# dmfboard.net
KiCad netlist of a schematic drawn in EAGLE
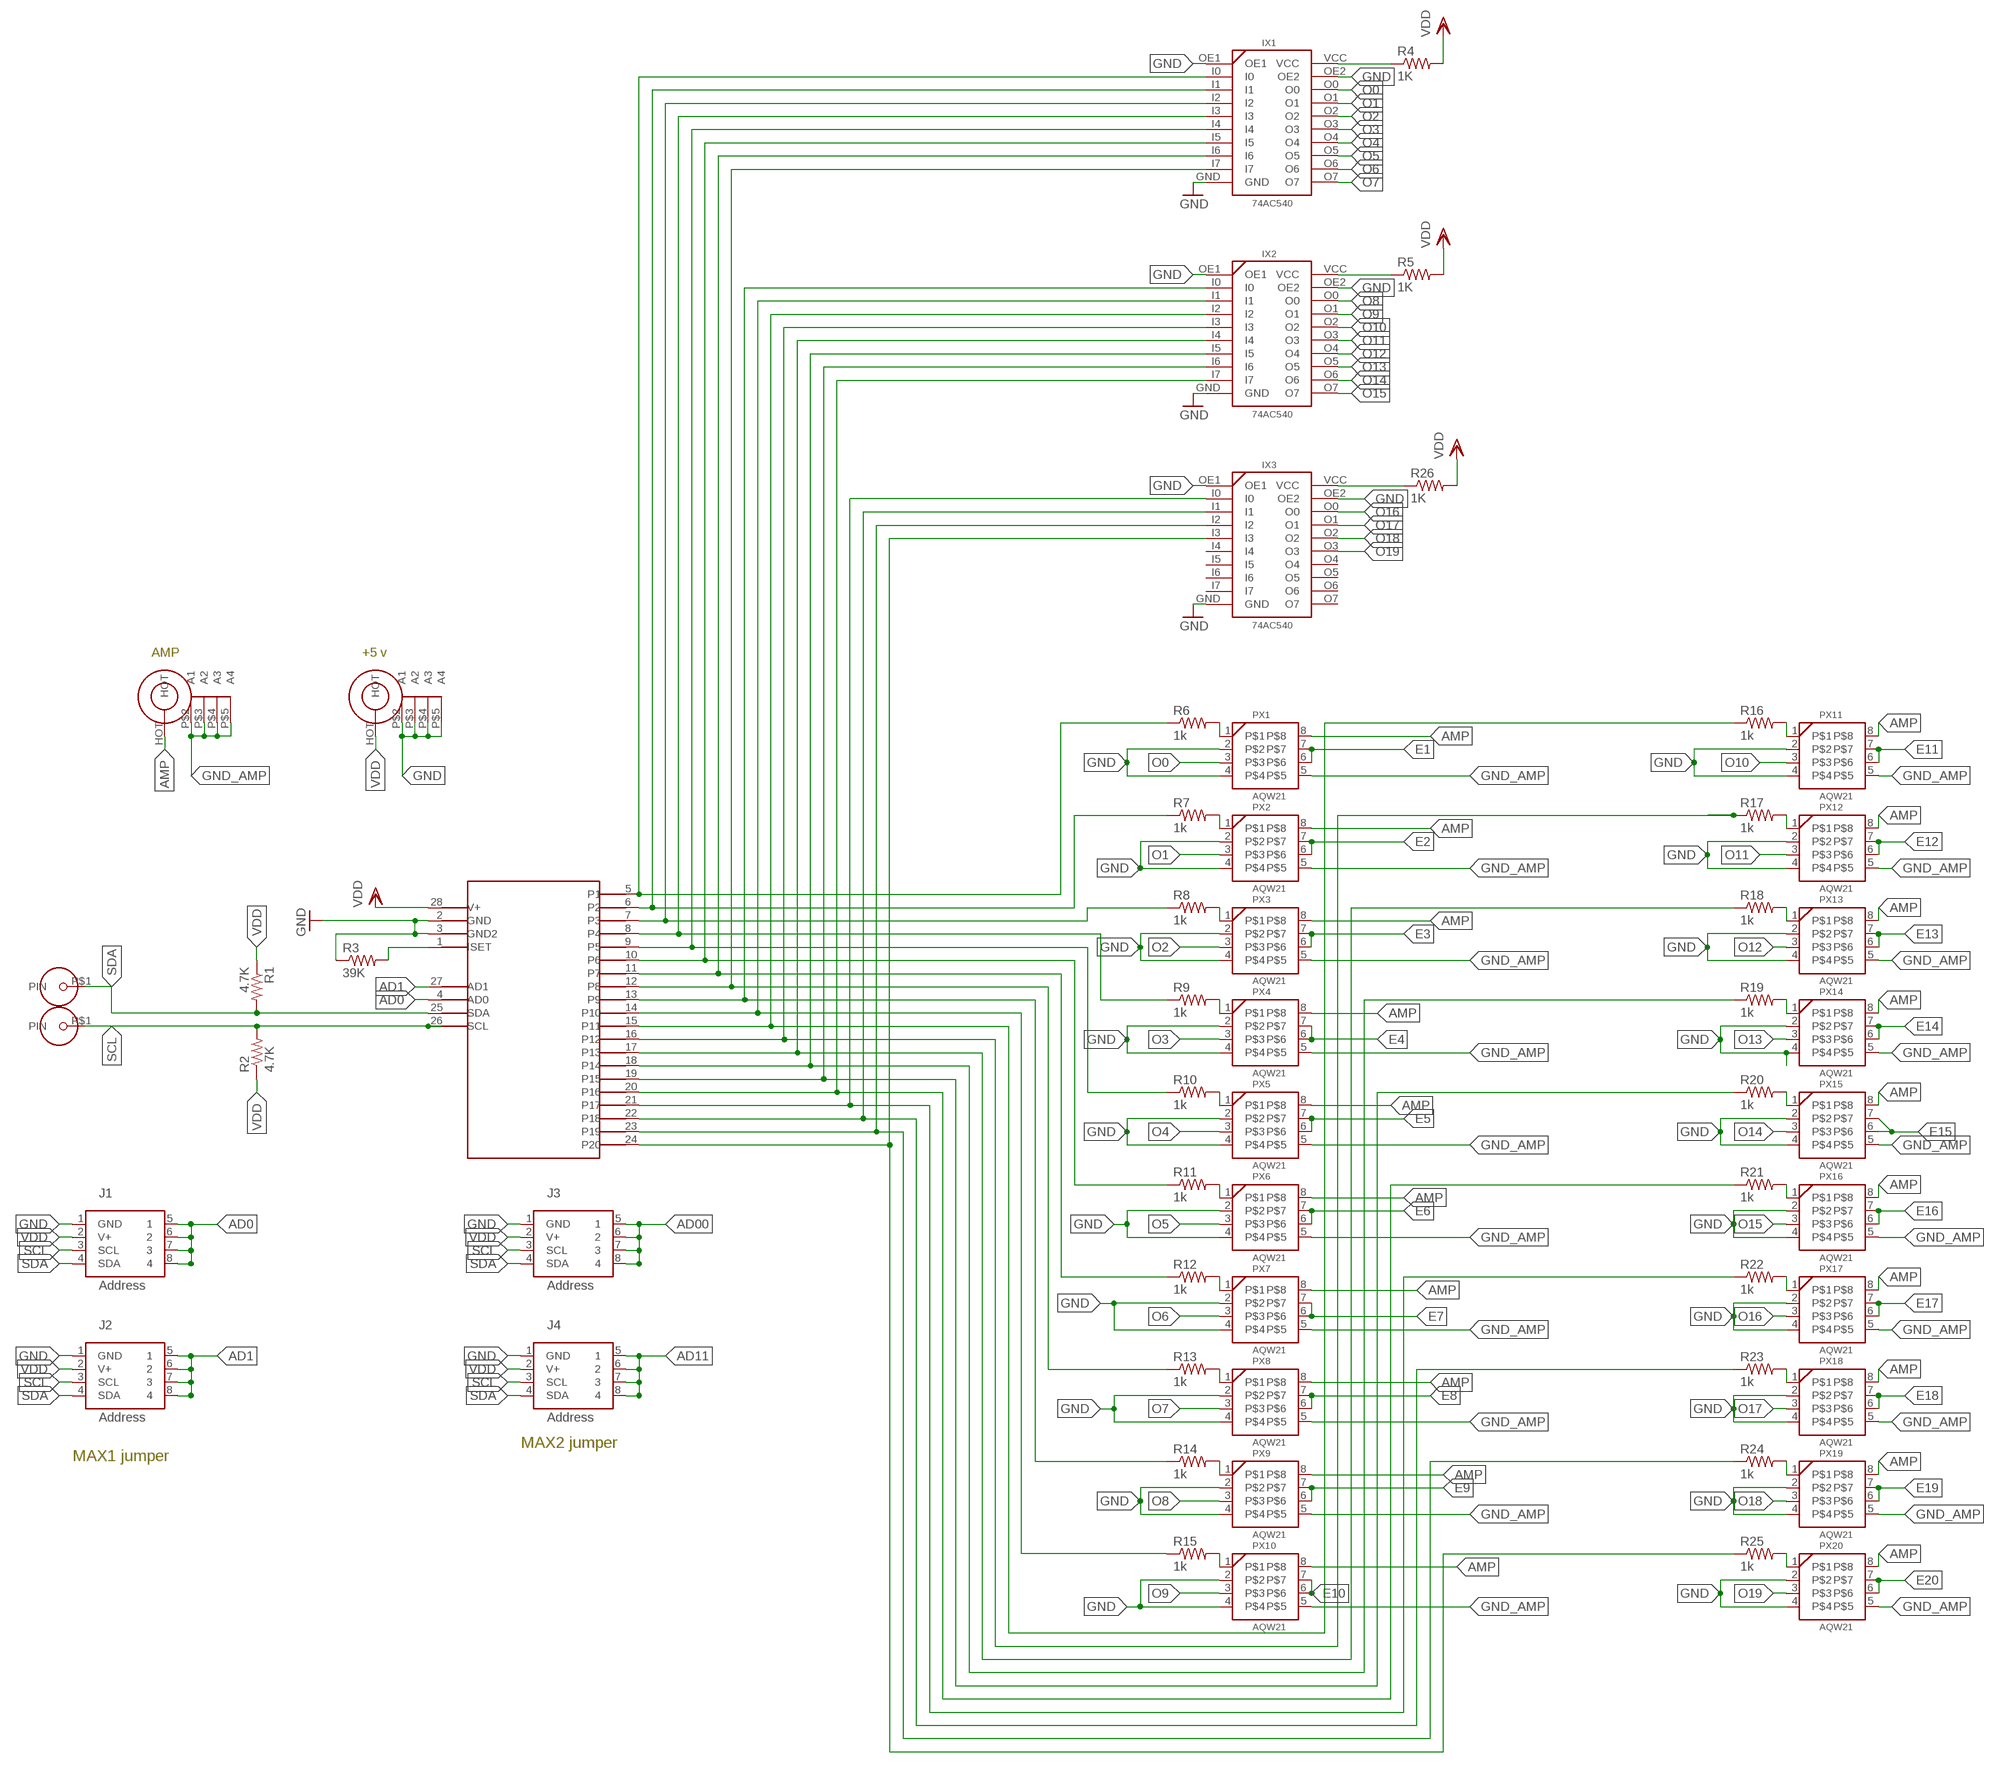
[diagram p0: schematic, sheet 1, part 1 of 2]
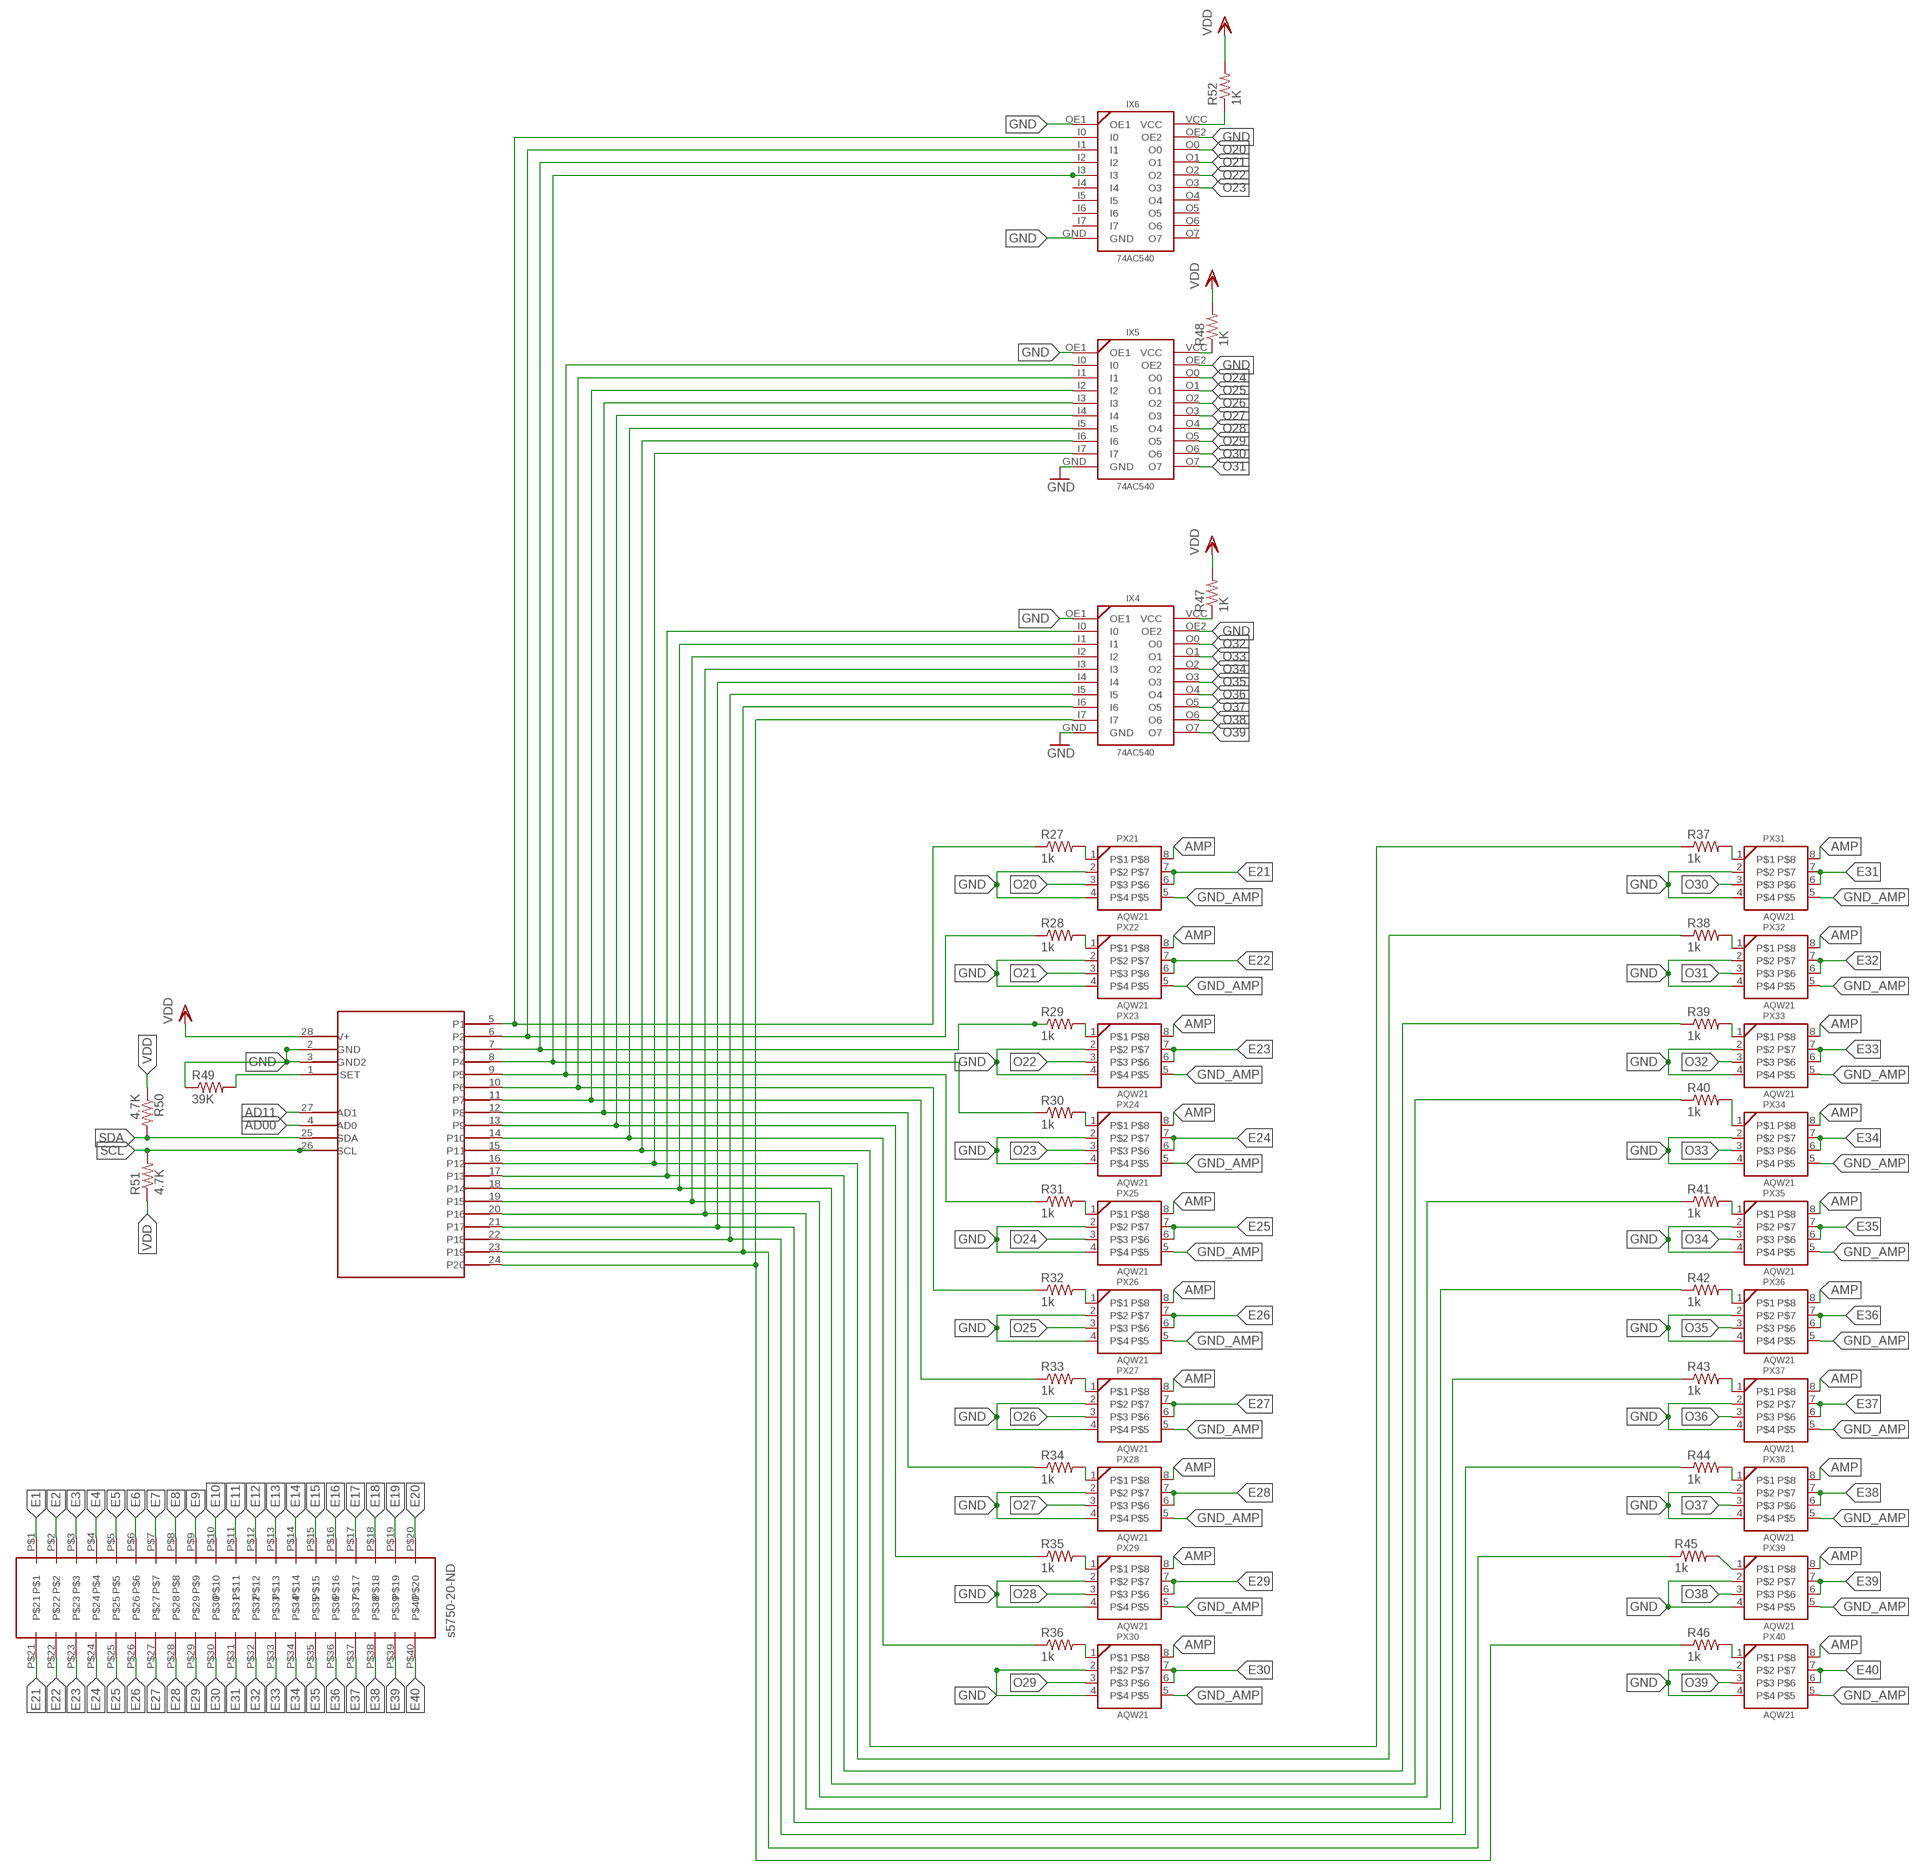
[diagram p1: schematic, sheet 1, part 2 of 2]

(export (version "E")
  (design (tool "Eeschema 10.0.6"))
  (components
    (comp (ref "5V")
      (value "BNC-BNC")
      (footprint "eagle-import:BNC-BNC")
      (libsource (lib "eagle-import") (part "BNC-BNC"))
    )
    (comp (ref "AMP")
      (value "BNC-BNC")
      (footprint "eagle-import:BNC-BNC")
      (libsource (lib "eagle-import") (part "BNC-BNC"))
    )
    (comp (ref "CONX1")
      (value "S5750_20_ND40PIN_CONNECTOR")
      (footprint "eagle-import:S5750-20_ND")
      (libsource (lib "eagle-import") (part "S5750_20_ND40PIN_CONNECTOR"))
    )
    (comp (ref "IX1")
      (value "74AC540")
      (footprint "eagle-import:SO20W")
      (libsource (lib "eagle-import") (part "74AC540"))
    )
    (comp (ref "IX2")
      (value "74AC540")
      (footprint "eagle-import:SO20W")
      (libsource (lib "eagle-import") (part "74AC540"))
    )
    (comp (ref "IX3")
      (value "74AC540")
      (footprint "eagle-import:SO20W")
      (libsource (lib "eagle-import") (part "74AC540"))
    )
    (comp (ref "IX4")
      (value "74AC540")
      (footprint "eagle-import:SO20W")
      (libsource (lib "eagle-import") (part "74AC540"))
    )
    (comp (ref "IX5")
      (value "74AC540")
      (footprint "eagle-import:SO20W")
      (libsource (lib "eagle-import") (part "74AC540"))
    )
    (comp (ref "IX6")
      (value "74AC540")
      (footprint "eagle-import:SO20W")
      (libsource (lib "eagle-import") (part "74AC540"))
    )
    (comp (ref "J1")
      (value "JUMPER")
      (footprint "eagle-import:JUMPER")
      (libsource (lib "eagle-import") (part "JUMPER"))
    )
    (comp (ref "J2")
      (value "JUMPER")
      (footprint "eagle-import:JUMPER")
      (libsource (lib "eagle-import") (part "JUMPER"))
    )
    (comp (ref "J3")
      (value "JUMPER")
      (footprint "eagle-import:JUMPER")
      (libsource (lib "eagle-import") (part "JUMPER"))
    )
    (comp (ref "J4")
      (value "JUMPER")
      (footprint "eagle-import:JUMPER")
      (libsource (lib "eagle-import") (part "JUMPER"))
    )
    (comp (ref "MX1")
      (value "MAX7300")
      (footprint "eagle-import:MAX7300")
      (libsource (lib "eagle-import") (part "MAX7300"))
    )
    (comp (ref "MX2")
      (value "MAX7300")
      (footprint "eagle-import:MAX7300")
      (libsource (lib "eagle-import") (part "MAX7300"))
    )
    (comp (ref "PX1")
      (value "AQW21")
      (footprint "eagle-import:AQW216EH")
      (libsource (lib "eagle-import") (part "AQW21"))
    )
    (comp (ref "PX2")
      (value "AQW21")
      (footprint "eagle-import:AQW216EH")
      (libsource (lib "eagle-import") (part "AQW21"))
    )
    (comp (ref "PX3")
      (value "AQW21")
      (footprint "eagle-import:AQW216EH")
      (libsource (lib "eagle-import") (part "AQW21"))
    )
    (comp (ref "PX4")
      (value "AQW21")
      (footprint "eagle-import:AQW216EH")
      (libsource (lib "eagle-import") (part "AQW21"))
    )
    (comp (ref "PX5")
      (value "AQW21")
      (footprint "eagle-import:AQW216EH")
      (libsource (lib "eagle-import") (part "AQW21"))
    )
    (comp (ref "PX6")
      (value "AQW21")
      (footprint "eagle-import:AQW216EH")
      (libsource (lib "eagle-import") (part "AQW21"))
    )
    (comp (ref "PX7")
      (value "AQW21")
      (footprint "eagle-import:AQW216EH")
      (libsource (lib "eagle-import") (part "AQW21"))
    )
    (comp (ref "PX8")
      (value "AQW21")
      (footprint "eagle-import:AQW216EH")
      (libsource (lib "eagle-import") (part "AQW21"))
    )
    (comp (ref "PX9")
      (value "AQW21")
      (footprint "eagle-import:AQW216EH")
      (libsource (lib "eagle-import") (part "AQW21"))
    )
    (comp (ref "PX10")
      (value "AQW21")
      (footprint "eagle-import:AQW216EH")
      (libsource (lib "eagle-import") (part "AQW21"))
    )
    (comp (ref "PX11")
      (value "AQW21")
      (footprint "eagle-import:AQW216EH")
      (libsource (lib "eagle-import") (part "AQW21"))
    )
    (comp (ref "PX12")
      (value "AQW21")
      (footprint "eagle-import:AQW216EH")
      (libsource (lib "eagle-import") (part "AQW21"))
    )
    (comp (ref "PX13")
      (value "AQW21")
      (footprint "eagle-import:AQW216EH")
      (libsource (lib "eagle-import") (part "AQW21"))
    )
    (comp (ref "PX14")
      (value "AQW21")
      (footprint "eagle-import:AQW216EH")
      (libsource (lib "eagle-import") (part "AQW21"))
    )
    (comp (ref "PX15")
      (value "AQW21")
      (footprint "eagle-import:AQW216EH")
      (libsource (lib "eagle-import") (part "AQW21"))
    )
    (comp (ref "PX16")
      (value "AQW21")
      (footprint "eagle-import:AQW216EH")
      (libsource (lib "eagle-import") (part "AQW21"))
    )
    (comp (ref "PX17")
      (value "AQW21")
      (footprint "eagle-import:AQW216EH")
      (libsource (lib "eagle-import") (part "AQW21"))
    )
    (comp (ref "PX18")
      (value "AQW21")
      (footprint "eagle-import:AQW216EH")
      (libsource (lib "eagle-import") (part "AQW21"))
    )
    (comp (ref "PX19")
      (value "AQW21")
      (footprint "eagle-import:AQW216EH")
      (libsource (lib "eagle-import") (part "AQW21"))
    )
    (comp (ref "PX20")
      (value "AQW21")
      (footprint "eagle-import:AQW216EH")
      (libsource (lib "eagle-import") (part "AQW21"))
    )
    (comp (ref "PX21")
      (value "AQW21")
      (footprint "eagle-import:AQW216EH")
      (libsource (lib "eagle-import") (part "AQW21"))
    )
    (comp (ref "PX22")
      (value "AQW21")
      (footprint "eagle-import:AQW216EH")
      (libsource (lib "eagle-import") (part "AQW21"))
    )
    (comp (ref "PX23")
      (value "AQW21")
      (footprint "eagle-import:AQW216EH")
      (libsource (lib "eagle-import") (part "AQW21"))
    )
    (comp (ref "PX24")
      (value "AQW21")
      (footprint "eagle-import:AQW216EH")
      (libsource (lib "eagle-import") (part "AQW21"))
    )
    (comp (ref "PX25")
      (value "AQW21")
      (footprint "eagle-import:AQW216EH")
      (libsource (lib "eagle-import") (part "AQW21"))
    )
    (comp (ref "PX26")
      (value "AQW21")
      (footprint "eagle-import:AQW216EH")
      (libsource (lib "eagle-import") (part "AQW21"))
    )
    (comp (ref "PX27")
      (value "AQW21")
      (footprint "eagle-import:AQW216EH")
      (libsource (lib "eagle-import") (part "AQW21"))
    )
    (comp (ref "PX28")
      (value "AQW21")
      (footprint "eagle-import:AQW216EH")
      (libsource (lib "eagle-import") (part "AQW21"))
    )
    (comp (ref "PX29")
      (value "AQW21")
      (footprint "eagle-import:AQW216EH")
      (libsource (lib "eagle-import") (part "AQW21"))
    )
    (comp (ref "PX30")
      (value "AQW21")
      (footprint "eagle-import:AQW216EH")
      (libsource (lib "eagle-import") (part "AQW21"))
    )
    (comp (ref "PX31")
      (value "AQW21")
      (footprint "eagle-import:AQW216EH")
      (libsource (lib "eagle-import") (part "AQW21"))
    )
    (comp (ref "PX32")
      (value "AQW21")
      (footprint "eagle-import:AQW216EH")
      (libsource (lib "eagle-import") (part "AQW21"))
    )
    (comp (ref "PX33")
      (value "AQW21")
      (footprint "eagle-import:AQW216EH")
      (libsource (lib "eagle-import") (part "AQW21"))
    )
    (comp (ref "PX34")
      (value "AQW21")
      (footprint "eagle-import:AQW216EH")
      (libsource (lib "eagle-import") (part "AQW21"))
    )
    (comp (ref "PX35")
      (value "AQW21")
      (footprint "eagle-import:AQW216EH")
      (libsource (lib "eagle-import") (part "AQW21"))
    )
    (comp (ref "PX36")
      (value "AQW21")
      (footprint "eagle-import:AQW216EH")
      (libsource (lib "eagle-import") (part "AQW21"))
    )
    (comp (ref "PX37")
      (value "AQW21")
      (footprint "eagle-import:AQW216EH")
      (libsource (lib "eagle-import") (part "AQW21"))
    )
    (comp (ref "PX38")
      (value "AQW21")
      (footprint "eagle-import:AQW216EH")
      (libsource (lib "eagle-import") (part "AQW21"))
    )
    (comp (ref "PX39")
      (value "AQW21")
      (footprint "eagle-import:AQW216EH")
      (libsource (lib "eagle-import") (part "AQW21"))
    )
    (comp (ref "PX40")
      (value "AQW21")
      (footprint "eagle-import:AQW216EH")
      (libsource (lib "eagle-import") (part "AQW21"))
    )
    (comp (ref "R1")
      (value "4.7K")
      (footprint "eagle-import:M0805")
      (libsource (lib "eagle-import") (part "R-US_M0805"))
    )
    (comp (ref "R2")
      (value "4.7K")
      (footprint "eagle-import:M0805")
      (libsource (lib "eagle-import") (part "R-US_M0805"))
    )
    (comp (ref "R3")
      (value "39K")
      (footprint "eagle-import:M0805")
      (libsource (lib "eagle-import") (part "R-US_M0805"))
    )
    (comp (ref "R4")
      (value "1K")
      (footprint "eagle-import:M0805")
      (libsource (lib "eagle-import") (part "R-US_M0805"))
    )
    (comp (ref "R5")
      (value "1K")
      (footprint "eagle-import:M0805")
      (libsource (lib "eagle-import") (part "R-US_M0805"))
    )
    (comp (ref "R6")
      (value "1k")
      (footprint "eagle-import:M0805")
      (libsource (lib "eagle-import") (part "R-US_M0805"))
    )
    (comp (ref "R7")
      (value "1k")
      (footprint "eagle-import:M0805")
      (libsource (lib "eagle-import") (part "R-US_M0805"))
    )
    (comp (ref "R8")
      (value "1k")
      (footprint "eagle-import:M0805")
      (libsource (lib "eagle-import") (part "R-US_M0805"))
    )
    (comp (ref "R9")
      (value "1k")
      (footprint "eagle-import:M0805")
      (libsource (lib "eagle-import") (part "R-US_M0805"))
    )
    (comp (ref "R10")
      (value "1k")
      (footprint "eagle-import:M0805")
      (libsource (lib "eagle-import") (part "R-US_M0805"))
    )
    (comp (ref "R11")
      (value "1k")
      (footprint "eagle-import:M0805")
      (libsource (lib "eagle-import") (part "R-US_M0805"))
    )
    (comp (ref "R12")
      (value "1k")
      (footprint "eagle-import:M0805")
      (libsource (lib "eagle-import") (part "R-US_M0805"))
    )
    (comp (ref "R13")
      (value "1k")
      (footprint "eagle-import:M0805")
      (libsource (lib "eagle-import") (part "R-US_M0805"))
    )
    (comp (ref "R14")
      (value "1k")
      (footprint "eagle-import:M0805")
      (libsource (lib "eagle-import") (part "R-US_M0805"))
    )
    (comp (ref "R15")
      (value "1k")
      (footprint "eagle-import:M0805")
      (libsource (lib "eagle-import") (part "R-US_M0805"))
    )
    (comp (ref "R16")
      (value "1k")
      (footprint "eagle-import:M0805")
      (libsource (lib "eagle-import") (part "R-US_M0805"))
    )
    (comp (ref "R17")
      (value "1k")
      (footprint "eagle-import:M0805")
      (libsource (lib "eagle-import") (part "R-US_M0805"))
    )
    (comp (ref "R18")
      (value "1k")
      (footprint "eagle-import:M0805")
      (libsource (lib "eagle-import") (part "R-US_M0805"))
    )
    (comp (ref "R19")
      (value "1k")
      (footprint "eagle-import:M0805")
      (libsource (lib "eagle-import") (part "R-US_M0805"))
    )
    (comp (ref "R20")
      (value "1k")
      (footprint "eagle-import:M0805")
      (libsource (lib "eagle-import") (part "R-US_M0805"))
    )
    (comp (ref "R21")
      (value "1k")
      (footprint "eagle-import:M0805")
      (libsource (lib "eagle-import") (part "R-US_M0805"))
    )
    (comp (ref "R22")
      (value "1k")
      (footprint "eagle-import:M0805")
      (libsource (lib "eagle-import") (part "R-US_M0805"))
    )
    (comp (ref "R23")
      (value "1k")
      (footprint "eagle-import:M0805")
      (libsource (lib "eagle-import") (part "R-US_M0805"))
    )
    (comp (ref "R24")
      (value "1k")
      (footprint "eagle-import:M0805")
      (libsource (lib "eagle-import") (part "R-US_M0805"))
    )
    (comp (ref "R25")
      (value "1k")
      (footprint "eagle-import:M0805")
      (libsource (lib "eagle-import") (part "R-US_M0805"))
    )
    (comp (ref "R26")
      (value "1K")
      (footprint "eagle-import:M0805")
      (libsource (lib "eagle-import") (part "R-US_M0805"))
    )
    (comp (ref "R27")
      (value "1k")
      (footprint "eagle-import:M0805")
      (libsource (lib "eagle-import") (part "R-US_M0805"))
    )
    (comp (ref "R28")
      (value "1k")
      (footprint "eagle-import:M0805")
      (libsource (lib "eagle-import") (part "R-US_M0805"))
    )
    (comp (ref "R29")
      (value "1k")
      (footprint "eagle-import:M0805")
      (libsource (lib "eagle-import") (part "R-US_M0805"))
    )
    (comp (ref "R30")
      (value "1k")
      (footprint "eagle-import:M0805")
      (libsource (lib "eagle-import") (part "R-US_M0805"))
    )
    (comp (ref "R31")
      (value "1k")
      (footprint "eagle-import:M0805")
      (libsource (lib "eagle-import") (part "R-US_M0805"))
    )
    (comp (ref "R32")
      (value "1k")
      (footprint "eagle-import:M0805")
      (libsource (lib "eagle-import") (part "R-US_M0805"))
    )
    (comp (ref "R33")
      (value "1k")
      (footprint "eagle-import:M0805")
      (libsource (lib "eagle-import") (part "R-US_M0805"))
    )
    (comp (ref "R34")
      (value "1k")
      (footprint "eagle-import:M0805")
      (libsource (lib "eagle-import") (part "R-US_M0805"))
    )
    (comp (ref "R35")
      (value "1k")
      (footprint "eagle-import:M0805")
      (libsource (lib "eagle-import") (part "R-US_M0805"))
    )
    (comp (ref "R36")
      (value "1k")
      (footprint "eagle-import:M0805")
      (libsource (lib "eagle-import") (part "R-US_M0805"))
    )
    (comp (ref "R37")
      (value "1k")
      (footprint "eagle-import:M0805")
      (libsource (lib "eagle-import") (part "R-US_M0805"))
    )
    (comp (ref "R38")
      (value "1k")
      (footprint "eagle-import:M0805")
      (libsource (lib "eagle-import") (part "R-US_M0805"))
    )
    (comp (ref "R39")
      (value "1k")
      (footprint "eagle-import:M0805")
      (libsource (lib "eagle-import") (part "R-US_M0805"))
    )
    (comp (ref "R40")
      (value "1k")
      (footprint "eagle-import:M0805")
      (libsource (lib "eagle-import") (part "R-US_M0805"))
    )
    (comp (ref "R41")
      (value "1k")
      (footprint "eagle-import:M0805")
      (libsource (lib "eagle-import") (part "R-US_M0805"))
    )
    (comp (ref "R42")
      (value "1k")
      (footprint "eagle-import:M0805")
      (libsource (lib "eagle-import") (part "R-US_M0805"))
    )
    (comp (ref "R43")
      (value "1k")
      (footprint "eagle-import:M0805")
      (libsource (lib "eagle-import") (part "R-US_M0805"))
    )
    (comp (ref "R44")
      (value "1k")
      (footprint "eagle-import:M0805")
      (libsource (lib "eagle-import") (part "R-US_M0805"))
    )
    (comp (ref "R45")
      (value "1k")
      (footprint "eagle-import:M0805")
      (libsource (lib "eagle-import") (part "R-US_M0805"))
    )
    (comp (ref "R46")
      (value "1k")
      (footprint "eagle-import:M0805")
      (libsource (lib "eagle-import") (part "R-US_M0805"))
    )
    (comp (ref "R47")
      (value "1K")
      (footprint "eagle-import:M0805")
      (libsource (lib "eagle-import") (part "R-US_M0805"))
    )
    (comp (ref "R48")
      (value "1K")
      (footprint "eagle-import:M0805")
      (libsource (lib "eagle-import") (part "R-US_M0805"))
    )
    (comp (ref "R49")
      (value "39K")
      (footprint "eagle-import:M0805")
      (libsource (lib "eagle-import") (part "R-US_M0805"))
    )
    (comp (ref "R50")
      (value "4.7K")
      (footprint "eagle-import:M0805")
      (libsource (lib "eagle-import") (part "R-US_M0805"))
    )
    (comp (ref "R51")
      (value "4.7K")
      (footprint "eagle-import:M0805")
      (libsource (lib "eagle-import") (part "R-US_M0805"))
    )
    (comp (ref "R52")
      (value "1K")
      (footprint "eagle-import:M0805")
      (libsource (lib "eagle-import") (part "R-US_M0805"))
    )
    (comp (ref "SCL")
      (value "TH_HOLE")
      (footprint "eagle-import:TH_PIN")
      (libsource (lib "eagle-import") (part "TH_HOLE"))
    )
    (comp (ref "SDA")
      (value "TH_HOLE")
      (footprint "eagle-import:TH_PIN")
      (libsource (lib "eagle-import") (part "TH_HOLE"))
    )
  )
  (nets
    (net (code "1") (name "AD00") (class "Default")
      (node (ref "J3") (pin "5") (pinfunction "1_5") (pintype "bidirectional"))
      (node (ref "J3") (pin "6") (pinfunction "2_6") (pintype "bidirectional"))
      (node (ref "J3") (pin "7") (pinfunction "3_7") (pintype "bidirectional"))
      (node (ref "J3") (pin "8") (pinfunction "4_8") (pintype "bidirectional"))
      (node (ref "MX2") (pin "4") (pinfunction "AD0_4") (pintype "bidirectional"))
    )
    (net (code "2") (name "AD0") (class "Default")
      (node (ref "J1") (pin "5") (pinfunction "1_5") (pintype "bidirectional"))
      (node (ref "J1") (pin "6") (pinfunction "2_6") (pintype "bidirectional"))
      (node (ref "J1") (pin "7") (pinfunction "3_7") (pintype "bidirectional"))
      (node (ref "J1") (pin "8") (pinfunction "4_8") (pintype "bidirectional"))
      (node (ref "MX1") (pin "4") (pinfunction "AD0_4") (pintype "bidirectional"))
    )
    (net (code "3") (name "AD1") (class "Default")
      (node (ref "J2") (pin "5") (pinfunction "1_5") (pintype "bidirectional"))
      (node (ref "J2") (pin "6") (pinfunction "2_6") (pintype "bidirectional"))
      (node (ref "J2") (pin "7") (pinfunction "3_7") (pintype "bidirectional"))
      (node (ref "J2") (pin "8") (pinfunction "4_8") (pintype "bidirectional"))
      (node (ref "MX1") (pin "27") (pinfunction "AD1_27") (pintype "bidirectional"))
    )
    (net (code "4") (name "AD11") (class "Default")
      (node (ref "J4") (pin "5") (pinfunction "1_5") (pintype "bidirectional"))
      (node (ref "J4") (pin "6") (pinfunction "2_6") (pintype "bidirectional"))
      (node (ref "J4") (pin "7") (pinfunction "3_7") (pintype "bidirectional"))
      (node (ref "J4") (pin "8") (pinfunction "4_8") (pintype "bidirectional"))
      (node (ref "MX2") (pin "27") (pinfunction "AD1_27") (pintype "bidirectional"))
    )
    (net (code "5") (name "AMP") (class "Default")
      (node (ref "AMP") (pin "HOT") (pinfunction "HOT_HOT") (pintype "bidirectional"))
      (node (ref "PX1") (pin "8") (pinfunction "P$8_8") (pintype "bidirectional"))
      (node (ref "PX10") (pin "8") (pinfunction "P$8_8") (pintype "bidirectional"))
      (node (ref "PX11") (pin "8") (pinfunction "P$8_8") (pintype "bidirectional"))
      (node (ref "PX12") (pin "8") (pinfunction "P$8_8") (pintype "bidirectional"))
      (node (ref "PX13") (pin "8") (pinfunction "P$8_8") (pintype "bidirectional"))
      (node (ref "PX14") (pin "8") (pinfunction "P$8_8") (pintype "bidirectional"))
      (node (ref "PX15") (pin "8") (pinfunction "P$8_8") (pintype "bidirectional"))
      (node (ref "PX16") (pin "8") (pinfunction "P$8_8") (pintype "bidirectional"))
      (node (ref "PX17") (pin "8") (pinfunction "P$8_8") (pintype "bidirectional"))
      (node (ref "PX18") (pin "8") (pinfunction "P$8_8") (pintype "bidirectional"))
      (node (ref "PX19") (pin "8") (pinfunction "P$8_8") (pintype "bidirectional"))
      (node (ref "PX2") (pin "8") (pinfunction "P$8_8") (pintype "bidirectional"))
      (node (ref "PX20") (pin "8") (pinfunction "P$8_8") (pintype "bidirectional"))
      (node (ref "PX21") (pin "8") (pinfunction "P$8_8") (pintype "bidirectional"))
      (node (ref "PX22") (pin "8") (pinfunction "P$8_8") (pintype "bidirectional"))
      (node (ref "PX23") (pin "8") (pinfunction "P$8_8") (pintype "bidirectional"))
      (node (ref "PX24") (pin "8") (pinfunction "P$8_8") (pintype "bidirectional"))
      (node (ref "PX25") (pin "8") (pinfunction "P$8_8") (pintype "bidirectional"))
      (node (ref "PX26") (pin "8") (pinfunction "P$8_8") (pintype "bidirectional"))
      (node (ref "PX27") (pin "8") (pinfunction "P$8_8") (pintype "bidirectional"))
      (node (ref "PX28") (pin "8") (pinfunction "P$8_8") (pintype "bidirectional"))
      (node (ref "PX29") (pin "8") (pinfunction "P$8_8") (pintype "bidirectional"))
      (node (ref "PX3") (pin "8") (pinfunction "P$8_8") (pintype "bidirectional"))
      (node (ref "PX30") (pin "8") (pinfunction "P$8_8") (pintype "bidirectional"))
      (node (ref "PX31") (pin "8") (pinfunction "P$8_8") (pintype "bidirectional"))
      (node (ref "PX32") (pin "8") (pinfunction "P$8_8") (pintype "bidirectional"))
      (node (ref "PX33") (pin "8") (pinfunction "P$8_8") (pintype "bidirectional"))
      (node (ref "PX34") (pin "8") (pinfunction "P$8_8") (pintype "bidirectional"))
      (node (ref "PX35") (pin "8") (pinfunction "P$8_8") (pintype "bidirectional"))
      (node (ref "PX36") (pin "8") (pinfunction "P$8_8") (pintype "bidirectional"))
      (node (ref "PX37") (pin "8") (pinfunction "P$8_8") (pintype "bidirectional"))
      (node (ref "PX38") (pin "8") (pinfunction "P$8_8") (pintype "bidirectional"))
      (node (ref "PX39") (pin "8") (pinfunction "P$8_8") (pintype "bidirectional"))
      (node (ref "PX4") (pin "8") (pinfunction "P$8_8") (pintype "bidirectional"))
      (node (ref "PX40") (pin "8") (pinfunction "P$8_8") (pintype "bidirectional"))
      (node (ref "PX5") (pin "8") (pinfunction "P$8_8") (pintype "bidirectional"))
      (node (ref "PX6") (pin "8") (pinfunction "P$8_8") (pintype "bidirectional"))
      (node (ref "PX7") (pin "8") (pinfunction "P$8_8") (pintype "bidirectional"))
      (node (ref "PX8") (pin "8") (pinfunction "P$8_8") (pintype "bidirectional"))
      (node (ref "PX9") (pin "8") (pinfunction "P$8_8") (pintype "bidirectional"))
    )
    (net (code "6") (name "E1") (class "Default")
      (node (ref "CONX1") (pin "P$1") (pinfunction "P$1_P$1") (pintype "bidirectional"))
      (node (ref "PX1") (pin "6") (pinfunction "P$6_6") (pintype "bidirectional"))
      (node (ref "PX1") (pin "7") (pinfunction "P$7_7") (pintype "bidirectional"))
    )
    (net (code "7") (name "E2") (class "Default")
      (node (ref "CONX1") (pin "P$2") (pinfunction "P$2_P$2") (pintype "bidirectional"))
      (node (ref "PX2") (pin "6") (pinfunction "P$6_6") (pintype "bidirectional"))
      (node (ref "PX2") (pin "7") (pinfunction "P$7_7") (pintype "bidirectional"))
    )
    (net (code "8") (name "E3") (class "Default")
      (node (ref "CONX1") (pin "P$3") (pinfunction "P$3_P$3") (pintype "bidirectional"))
      (node (ref "PX3") (pin "6") (pinfunction "P$6_6") (pintype "bidirectional"))
      (node (ref "PX3") (pin "7") (pinfunction "P$7_7") (pintype "bidirectional"))
    )
    (net (code "9") (name "E4") (class "Default")
      (node (ref "CONX1") (pin "P$4") (pinfunction "P$4_P$4") (pintype "bidirectional"))
      (node (ref "PX4") (pin "6") (pinfunction "P$6_6") (pintype "bidirectional"))
      (node (ref "PX4") (pin "7") (pinfunction "P$7_7") (pintype "bidirectional"))
    )
    (net (code "10") (name "E5") (class "Default")
      (node (ref "CONX1") (pin "P$5") (pinfunction "P$5_P$5") (pintype "bidirectional"))
      (node (ref "PX5") (pin "6") (pinfunction "P$6_6") (pintype "bidirectional"))
      (node (ref "PX5") (pin "7") (pinfunction "P$7_7") (pintype "bidirectional"))
    )
    (net (code "11") (name "E6") (class "Default")
      (node (ref "CONX1") (pin "P$6") (pinfunction "P$6_P$6") (pintype "bidirectional"))
      (node (ref "PX6") (pin "6") (pinfunction "P$6_6") (pintype "bidirectional"))
      (node (ref "PX6") (pin "7") (pinfunction "P$7_7") (pintype "bidirectional"))
    )
    (net (code "12") (name "E7") (class "Default")
      (node (ref "CONX1") (pin "P$7") (pinfunction "P$7_P$7") (pintype "bidirectional"))
      (node (ref "PX7") (pin "6") (pinfunction "P$6_6") (pintype "bidirectional"))
      (node (ref "PX7") (pin "7") (pinfunction "P$7_7") (pintype "bidirectional"))
    )
    (net (code "13") (name "E8") (class "Default")
      (node (ref "CONX1") (pin "P$8") (pinfunction "P$8_P$8") (pintype "bidirectional"))
      (node (ref "PX8") (pin "6") (pinfunction "P$6_6") (pintype "bidirectional"))
      (node (ref "PX8") (pin "7") (pinfunction "P$7_7") (pintype "bidirectional"))
    )
    (net (code "14") (name "E9") (class "Default")
      (node (ref "CONX1") (pin "P$9") (pinfunction "P$9_P$9") (pintype "bidirectional"))
      (node (ref "PX9") (pin "6") (pinfunction "P$6_6") (pintype "bidirectional"))
      (node (ref "PX9") (pin "7") (pinfunction "P$7_7") (pintype "bidirectional"))
    )
    (net (code "15") (name "E10") (class "Default")
      (node (ref "CONX1") (pin "P$10") (pinfunction "P$10_P$10") (pintype "bidirectional"))
      (node (ref "PX10") (pin "6") (pinfunction "P$6_6") (pintype "bidirectional"))
      (node (ref "PX10") (pin "7") (pinfunction "P$7_7") (pintype "bidirectional"))
    )
    (net (code "16") (name "E11") (class "Default")
      (node (ref "CONX1") (pin "P$11") (pinfunction "P$11_P$11") (pintype "bidirectional"))
      (node (ref "PX11") (pin "6") (pinfunction "P$6_6") (pintype "bidirectional"))
      (node (ref "PX11") (pin "7") (pinfunction "P$7_7") (pintype "bidirectional"))
    )
    (net (code "17") (name "E12") (class "Default")
      (node (ref "CONX1") (pin "P$12") (pinfunction "P$12_P$12") (pintype "bidirectional"))
      (node (ref "PX12") (pin "6") (pinfunction "P$6_6") (pintype "bidirectional"))
      (node (ref "PX12") (pin "7") (pinfunction "P$7_7") (pintype "bidirectional"))
    )
    (net (code "18") (name "E13") (class "Default")
      (node (ref "CONX1") (pin "P$13") (pinfunction "P$13_P$13") (pintype "bidirectional"))
      (node (ref "PX13") (pin "6") (pinfunction "P$6_6") (pintype "bidirectional"))
      (node (ref "PX13") (pin "7") (pinfunction "P$7_7") (pintype "bidirectional"))
    )
    (net (code "19") (name "E14") (class "Default")
      (node (ref "CONX1") (pin "P$14") (pinfunction "P$14_P$14") (pintype "bidirectional"))
      (node (ref "PX14") (pin "6") (pinfunction "P$6_6") (pintype "bidirectional"))
      (node (ref "PX14") (pin "7") (pinfunction "P$7_7") (pintype "bidirectional"))
    )
    (net (code "20") (name "E15") (class "Default")
      (node (ref "CONX1") (pin "P$15") (pinfunction "P$15_P$15") (pintype "bidirectional"))
      (node (ref "PX15") (pin "6") (pinfunction "P$6_6") (pintype "bidirectional"))
      (node (ref "PX15") (pin "7") (pinfunction "P$7_7") (pintype "bidirectional"))
    )
    (net (code "21") (name "E16") (class "Default")
      (node (ref "CONX1") (pin "P$16") (pinfunction "P$16_P$16") (pintype "bidirectional"))
      (node (ref "PX16") (pin "6") (pinfunction "P$6_6") (pintype "bidirectional"))
      (node (ref "PX16") (pin "7") (pinfunction "P$7_7") (pintype "bidirectional"))
    )
    (net (code "22") (name "E17") (class "Default")
      (node (ref "CONX1") (pin "P$17") (pinfunction "P$17_P$17") (pintype "bidirectional"))
      (node (ref "PX17") (pin "6") (pinfunction "P$6_6") (pintype "bidirectional"))
      (node (ref "PX17") (pin "7") (pinfunction "P$7_7") (pintype "bidirectional"))
    )
    (net (code "23") (name "E18") (class "Default")
      (node (ref "CONX1") (pin "P$18") (pinfunction "P$18_P$18") (pintype "bidirectional"))
      (node (ref "PX18") (pin "6") (pinfunction "P$6_6") (pintype "bidirectional"))
      (node (ref "PX18") (pin "7") (pinfunction "P$7_7") (pintype "bidirectional"))
    )
    (net (code "24") (name "E19") (class "Default")
      (node (ref "CONX1") (pin "P$19") (pinfunction "P$19_P$19") (pintype "bidirectional"))
      (node (ref "PX19") (pin "6") (pinfunction "P$6_6") (pintype "bidirectional"))
      (node (ref "PX19") (pin "7") (pinfunction "P$7_7") (pintype "bidirectional"))
    )
    (net (code "25") (name "E20") (class "Default")
      (node (ref "CONX1") (pin "P$20") (pinfunction "P$20_P$20") (pintype "bidirectional"))
      (node (ref "PX20") (pin "6") (pinfunction "P$6_6") (pintype "bidirectional"))
      (node (ref "PX20") (pin "7") (pinfunction "P$7_7") (pintype "bidirectional"))
    )
    (net (code "26") (name "E21") (class "Default")
      (node (ref "CONX1") (pin "P$21") (pinfunction "P$21_P$21") (pintype "bidirectional"))
      (node (ref "PX21") (pin "6") (pinfunction "P$6_6") (pintype "bidirectional"))
      (node (ref "PX21") (pin "7") (pinfunction "P$7_7") (pintype "bidirectional"))
    )
    (net (code "27") (name "E22") (class "Default")
      (node (ref "CONX1") (pin "P$22") (pinfunction "P$22_P$22") (pintype "bidirectional"))
      (node (ref "PX22") (pin "6") (pinfunction "P$6_6") (pintype "bidirectional"))
      (node (ref "PX22") (pin "7") (pinfunction "P$7_7") (pintype "bidirectional"))
    )
    (net (code "28") (name "E23") (class "Default")
      (node (ref "CONX1") (pin "P$23") (pinfunction "P$23_P$23") (pintype "bidirectional"))
      (node (ref "PX23") (pin "6") (pinfunction "P$6_6") (pintype "bidirectional"))
      (node (ref "PX23") (pin "7") (pinfunction "P$7_7") (pintype "bidirectional"))
    )
    (net (code "29") (name "E24") (class "Default")
      (node (ref "CONX1") (pin "P$24") (pinfunction "P$24_P$24") (pintype "bidirectional"))
      (node (ref "PX24") (pin "6") (pinfunction "P$6_6") (pintype "bidirectional"))
      (node (ref "PX24") (pin "7") (pinfunction "P$7_7") (pintype "bidirectional"))
    )
    (net (code "30") (name "E25") (class "Default")
      (node (ref "CONX1") (pin "P$25") (pinfunction "P$25_P$25") (pintype "bidirectional"))
      (node (ref "PX25") (pin "6") (pinfunction "P$6_6") (pintype "bidirectional"))
      (node (ref "PX25") (pin "7") (pinfunction "P$7_7") (pintype "bidirectional"))
    )
    (net (code "31") (name "E26") (class "Default")
      (node (ref "CONX1") (pin "P$26") (pinfunction "P$26_P$26") (pintype "bidirectional"))
      (node (ref "PX26") (pin "6") (pinfunction "P$6_6") (pintype "bidirectional"))
      (node (ref "PX26") (pin "7") (pinfunction "P$7_7") (pintype "bidirectional"))
    )
    (net (code "32") (name "E27") (class "Default")
      (node (ref "CONX1") (pin "P$27") (pinfunction "P$27_P$27") (pintype "bidirectional"))
      (node (ref "PX27") (pin "6") (pinfunction "P$6_6") (pintype "bidirectional"))
      (node (ref "PX27") (pin "7") (pinfunction "P$7_7") (pintype "bidirectional"))
    )
    (net (code "33") (name "E28") (class "Default")
      (node (ref "CONX1") (pin "P$28") (pinfunction "P$28_P$28") (pintype "bidirectional"))
      (node (ref "PX28") (pin "6") (pinfunction "P$6_6") (pintype "bidirectional"))
      (node (ref "PX28") (pin "7") (pinfunction "P$7_7") (pintype "bidirectional"))
    )
    (net (code "34") (name "E29") (class "Default")
      (node (ref "CONX1") (pin "P$29") (pinfunction "P$29_P$29") (pintype "bidirectional"))
      (node (ref "PX29") (pin "6") (pinfunction "P$6_6") (pintype "bidirectional"))
      (node (ref "PX29") (pin "7") (pinfunction "P$7_7") (pintype "bidirectional"))
    )
    (net (code "35") (name "E30") (class "Default")
      (node (ref "CONX1") (pin "P$30") (pinfunction "P$30_P$30") (pintype "bidirectional"))
      (node (ref "PX30") (pin "6") (pinfunction "P$6_6") (pintype "bidirectional"))
      (node (ref "PX30") (pin "7") (pinfunction "P$7_7") (pintype "bidirectional"))
    )
    (net (code "36") (name "E31") (class "Default")
      (node (ref "CONX1") (pin "P$31") (pinfunction "P$31_P$31") (pintype "bidirectional"))
      (node (ref "PX31") (pin "6") (pinfunction "P$6_6") (pintype "bidirectional"))
      (node (ref "PX31") (pin "7") (pinfunction "P$7_7") (pintype "bidirectional"))
    )
    (net (code "37") (name "E32") (class "Default")
      (node (ref "CONX1") (pin "P$32") (pinfunction "P$32_P$32") (pintype "bidirectional"))
      (node (ref "PX32") (pin "6") (pinfunction "P$6_6") (pintype "bidirectional"))
      (node (ref "PX32") (pin "7") (pinfunction "P$7_7") (pintype "bidirectional"))
    )
    (net (code "38") (name "E33") (class "Default")
      (node (ref "CONX1") (pin "P$33") (pinfunction "P$33_P$33") (pintype "bidirectional"))
      (node (ref "PX33") (pin "6") (pinfunction "P$6_6") (pintype "bidirectional"))
      (node (ref "PX33") (pin "7") (pinfunction "P$7_7") (pintype "bidirectional"))
    )
    (net (code "39") (name "E34") (class "Default")
      (node (ref "CONX1") (pin "P$34") (pinfunction "P$34_P$34") (pintype "bidirectional"))
      (node (ref "PX34") (pin "6") (pinfunction "P$6_6") (pintype "bidirectional"))
      (node (ref "PX34") (pin "7") (pinfunction "P$7_7") (pintype "bidirectional"))
    )
    (net (code "40") (name "E35") (class "Default")
      (node (ref "CONX1") (pin "P$35") (pinfunction "P$35_P$35") (pintype "bidirectional"))
      (node (ref "PX35") (pin "6") (pinfunction "P$6_6") (pintype "bidirectional"))
      (node (ref "PX35") (pin "7") (pinfunction "P$7_7") (pintype "bidirectional"))
    )
    (net (code "41") (name "E36") (class "Default")
      (node (ref "CONX1") (pin "P$36") (pinfunction "P$36_P$36") (pintype "bidirectional"))
      (node (ref "PX36") (pin "6") (pinfunction "P$6_6") (pintype "bidirectional"))
      (node (ref "PX36") (pin "7") (pinfunction "P$7_7") (pintype "bidirectional"))
    )
    (net (code "42") (name "E37") (class "Default")
      (node (ref "CONX1") (pin "P$37") (pinfunction "P$37_P$37") (pintype "bidirectional"))
      (node (ref "PX37") (pin "6") (pinfunction "P$6_6") (pintype "bidirectional"))
      (node (ref "PX37") (pin "7") (pinfunction "P$7_7") (pintype "bidirectional"))
    )
    (net (code "43") (name "E38") (class "Default")
      (node (ref "CONX1") (pin "P$38") (pinfunction "P$38_P$38") (pintype "bidirectional"))
      (node (ref "PX38") (pin "6") (pinfunction "P$6_6") (pintype "bidirectional"))
      (node (ref "PX38") (pin "7") (pinfunction "P$7_7") (pintype "bidirectional"))
    )
    (net (code "44") (name "E39") (class "Default")
      (node (ref "CONX1") (pin "P$39") (pinfunction "P$39_P$39") (pintype "bidirectional"))
      (node (ref "PX39") (pin "6") (pinfunction "P$6_6") (pintype "bidirectional"))
      (node (ref "PX39") (pin "7") (pinfunction "P$7_7") (pintype "bidirectional"))
    )
    (net (code "45") (name "E40") (class "Default")
      (node (ref "CONX1") (pin "P$40") (pinfunction "P$40_P$40") (pintype "bidirectional"))
      (node (ref "PX40") (pin "6") (pinfunction "P$6_6") (pintype "bidirectional"))
      (node (ref "PX40") (pin "7") (pinfunction "P$7_7") (pintype "bidirectional"))
    )
    (net (code "46") (name "GND") (class "Default")
      (node (ref "5V") (pin "P$2") (pinfunction "A1_P$2") (pintype "bidirectional"))
      (node (ref "5V") (pin "P$3") (pinfunction "A2_P$3") (pintype "bidirectional"))
      (node (ref "5V") (pin "P$4") (pinfunction "A3_P$4") (pintype "bidirectional"))
      (node (ref "5V") (pin "P$5") (pinfunction "A4_P$5") (pintype "bidirectional"))
      (node (ref "IX1") (pin "GND") (pinfunction "GND_GND") (pintype "bidirectional"))
      (node (ref "IX1") (pin "OE1") (pinfunction "OE1_OE1") (pintype "bidirectional"))
      (node (ref "IX1") (pin "OE2") (pinfunction "OE2_OE2") (pintype "bidirectional"))
      (node (ref "IX2") (pin "GND") (pinfunction "GND_GND") (pintype "bidirectional"))
      (node (ref "IX2") (pin "OE1") (pinfunction "OE1_OE1") (pintype "bidirectional"))
      (node (ref "IX2") (pin "OE2") (pinfunction "OE2_OE2") (pintype "bidirectional"))
      (node (ref "IX3") (pin "GND") (pinfunction "GND_GND") (pintype "bidirectional"))
      (node (ref "IX3") (pin "OE1") (pinfunction "OE1_OE1") (pintype "bidirectional"))
      (node (ref "IX3") (pin "OE2") (pinfunction "OE2_OE2") (pintype "bidirectional"))
      (node (ref "IX4") (pin "GND") (pinfunction "GND_GND") (pintype "bidirectional"))
      (node (ref "IX4") (pin "OE1") (pinfunction "OE1_OE1") (pintype "bidirectional"))
      (node (ref "IX4") (pin "OE2") (pinfunction "OE2_OE2") (pintype "bidirectional"))
      (node (ref "IX5") (pin "GND") (pinfunction "GND_GND") (pintype "bidirectional"))
      (node (ref "IX5") (pin "OE1") (pinfunction "OE1_OE1") (pintype "bidirectional"))
      (node (ref "IX5") (pin "OE2") (pinfunction "OE2_OE2") (pintype "bidirectional"))
      (node (ref "IX6") (pin "GND") (pinfunction "GND_GND") (pintype "bidirectional"))
      (node (ref "IX6") (pin "OE1") (pinfunction "OE1_OE1") (pintype "bidirectional"))
      (node (ref "IX6") (pin "OE2") (pinfunction "OE2_OE2") (pintype "bidirectional"))
      (node (ref "J1") (pin "1") (pinfunction "GND_1") (pintype "bidirectional"))
      (node (ref "J2") (pin "1") (pinfunction "GND_1") (pintype "bidirectional"))
      (node (ref "J3") (pin "1") (pinfunction "GND_1") (pintype "bidirectional"))
      (node (ref "J4") (pin "1") (pinfunction "GND_1") (pintype "bidirectional"))
      (node (ref "MX1") (pin "2") (pinfunction "GND_2") (pintype "bidirectional"))
      (node (ref "MX1") (pin "3") (pinfunction "GND2_3") (pintype "bidirectional"))
      (node (ref "MX2") (pin "2") (pinfunction "GND_2") (pintype "bidirectional"))
      (node (ref "MX2") (pin "3") (pinfunction "GND2_3") (pintype "bidirectional"))
      (node (ref "PX1") (pin "2") (pinfunction "P$2_2") (pintype "bidirectional"))
      (node (ref "PX1") (pin "4") (pinfunction "P$4_4") (pintype "bidirectional"))
      (node (ref "PX10") (pin "2") (pinfunction "P$2_2") (pintype "bidirectional"))
      (node (ref "PX10") (pin "4") (pinfunction "P$4_4") (pintype "bidirectional"))
      (node (ref "PX11") (pin "2") (pinfunction "P$2_2") (pintype "bidirectional"))
      (node (ref "PX11") (pin "4") (pinfunction "P$4_4") (pintype "bidirectional"))
      (node (ref "PX12") (pin "2") (pinfunction "P$2_2") (pintype "bidirectional"))
      (node (ref "PX12") (pin "4") (pinfunction "P$4_4") (pintype "bidirectional"))
      (node (ref "PX13") (pin "2") (pinfunction "P$2_2") (pintype "bidirectional"))
      (node (ref "PX13") (pin "4") (pinfunction "P$4_4") (pintype "bidirectional"))
      (node (ref "PX14") (pin "2") (pinfunction "P$2_2") (pintype "bidirectional"))
      (node (ref "PX14") (pin "4") (pinfunction "P$4_4") (pintype "bidirectional"))
      (node (ref "PX15") (pin "2") (pinfunction "P$2_2") (pintype "bidirectional"))
      (node (ref "PX15") (pin "4") (pinfunction "P$4_4") (pintype "bidirectional"))
      (node (ref "PX16") (pin "2") (pinfunction "P$2_2") (pintype "bidirectional"))
      (node (ref "PX16") (pin "4") (pinfunction "P$4_4") (pintype "bidirectional"))
      (node (ref "PX17") (pin "2") (pinfunction "P$2_2") (pintype "bidirectional"))
      (node (ref "PX17") (pin "4") (pinfunction "P$4_4") (pintype "bidirectional"))
      (node (ref "PX18") (pin "2") (pinfunction "P$2_2") (pintype "bidirectional"))
      (node (ref "PX18") (pin "4") (pinfunction "P$4_4") (pintype "bidirectional"))
      (node (ref "PX19") (pin "2") (pinfunction "P$2_2") (pintype "bidirectional"))
      (node (ref "PX19") (pin "4") (pinfunction "P$4_4") (pintype "bidirectional"))
      (node (ref "PX2") (pin "2") (pinfunction "P$2_2") (pintype "bidirectional"))
      (node (ref "PX2") (pin "4") (pinfunction "P$4_4") (pintype "bidirectional"))
      (node (ref "PX20") (pin "2") (pinfunction "P$2_2") (pintype "bidirectional"))
      (node (ref "PX20") (pin "4") (pinfunction "P$4_4") (pintype "bidirectional"))
      (node (ref "PX21") (pin "2") (pinfunction "P$2_2") (pintype "bidirectional"))
      (node (ref "PX21") (pin "4") (pinfunction "P$4_4") (pintype "bidirectional"))
      (node (ref "PX22") (pin "2") (pinfunction "P$2_2") (pintype "bidirectional"))
      (node (ref "PX22") (pin "4") (pinfunction "P$4_4") (pintype "bidirectional"))
      (node (ref "PX23") (pin "2") (pinfunction "P$2_2") (pintype "bidirectional"))
      (node (ref "PX23") (pin "4") (pinfunction "P$4_4") (pintype "bidirectional"))
      (node (ref "PX24") (pin "2") (pinfunction "P$2_2") (pintype "bidirectional"))
      (node (ref "PX24") (pin "4") (pinfunction "P$4_4") (pintype "bidirectional"))
      (node (ref "PX25") (pin "2") (pinfunction "P$2_2") (pintype "bidirectional"))
      (node (ref "PX25") (pin "4") (pinfunction "P$4_4") (pintype "bidirectional"))
      (node (ref "PX26") (pin "2") (pinfunction "P$2_2") (pintype "bidirectional"))
      (node (ref "PX26") (pin "4") (pinfunction "P$4_4") (pintype "bidirectional"))
      (node (ref "PX27") (pin "2") (pinfunction "P$2_2") (pintype "bidirectional"))
      (node (ref "PX27") (pin "4") (pinfunction "P$4_4") (pintype "bidirectional"))
      (node (ref "PX28") (pin "2") (pinfunction "P$2_2") (pintype "bidirectional"))
      (node (ref "PX28") (pin "4") (pinfunction "P$4_4") (pintype "bidirectional"))
      (node (ref "PX29") (pin "2") (pinfunction "P$2_2") (pintype "bidirectional"))
      (node (ref "PX29") (pin "4") (pinfunction "P$4_4") (pintype "bidirectional"))
      (node (ref "PX3") (pin "2") (pinfunction "P$2_2") (pintype "bidirectional"))
      (node (ref "PX3") (pin "4") (pinfunction "P$4_4") (pintype "bidirectional"))
      (node (ref "PX30") (pin "2") (pinfunction "P$2_2") (pintype "bidirectional"))
      (node (ref "PX30") (pin "4") (pinfunction "P$4_4") (pintype "bidirectional"))
      (node (ref "PX31") (pin "2") (pinfunction "P$2_2") (pintype "bidirectional"))
      (node (ref "PX31") (pin "4") (pinfunction "P$4_4") (pintype "bidirectional"))
      (node (ref "PX32") (pin "2") (pinfunction "P$2_2") (pintype "bidirectional"))
      (node (ref "PX32") (pin "4") (pinfunction "P$4_4") (pintype "bidirectional"))
      (node (ref "PX33") (pin "2") (pinfunction "P$2_2") (pintype "bidirectional"))
      (node (ref "PX33") (pin "4") (pinfunction "P$4_4") (pintype "bidirectional"))
      (node (ref "PX34") (pin "2") (pinfunction "P$2_2") (pintype "bidirectional"))
      (node (ref "PX34") (pin "4") (pinfunction "P$4_4") (pintype "bidirectional"))
      (node (ref "PX35") (pin "2") (pinfunction "P$2_2") (pintype "bidirectional"))
      (node (ref "PX35") (pin "4") (pinfunction "P$4_4") (pintype "bidirectional"))
      (node (ref "PX36") (pin "2") (pinfunction "P$2_2") (pintype "bidirectional"))
      (node (ref "PX36") (pin "4") (pinfunction "P$4_4") (pintype "bidirectional"))
      (node (ref "PX37") (pin "2") (pinfunction "P$2_2") (pintype "bidirectional"))
      (node (ref "PX37") (pin "4") (pinfunction "P$4_4") (pintype "bidirectional"))
      (node (ref "PX38") (pin "2") (pinfunction "P$2_2") (pintype "bidirectional"))
      (node (ref "PX38") (pin "4") (pinfunction "P$4_4") (pintype "bidirectional"))
      (node (ref "PX39") (pin "2") (pinfunction "P$2_2") (pintype "bidirectional"))
      (node (ref "PX39") (pin "4") (pinfunction "P$4_4") (pintype "bidirectional"))
      (node (ref "PX4") (pin "2") (pinfunction "P$2_2") (pintype "bidirectional"))
      (node (ref "PX4") (pin "4") (pinfunction "P$4_4") (pintype "bidirectional"))
      (node (ref "PX40") (pin "2") (pinfunction "P$2_2") (pintype "bidirectional"))
      (node (ref "PX40") (pin "4") (pinfunction "P$4_4") (pintype "bidirectional"))
      (node (ref "PX5") (pin "2") (pinfunction "P$2_2") (pintype "bidirectional"))
      (node (ref "PX5") (pin "4") (pinfunction "P$4_4") (pintype "bidirectional"))
      (node (ref "PX6") (pin "2") (pinfunction "P$2_2") (pintype "bidirectional"))
      (node (ref "PX6") (pin "4") (pinfunction "P$4_4") (pintype "bidirectional"))
      (node (ref "PX7") (pin "2") (pinfunction "P$2_2") (pintype "bidirectional"))
      (node (ref "PX7") (pin "4") (pinfunction "P$4_4") (pintype "bidirectional"))
      (node (ref "PX8") (pin "2") (pinfunction "P$2_2") (pintype "bidirectional"))
      (node (ref "PX8") (pin "4") (pinfunction "P$4_4") (pintype "bidirectional"))
      (node (ref "PX9") (pin "2") (pinfunction "P$2_2") (pintype "bidirectional"))
      (node (ref "PX9") (pin "4") (pinfunction "P$4_4") (pintype "bidirectional"))
      (node (ref "R3") (pin "1") (pinfunction "1_1") (pintype "passive"))
      (node (ref "R49") (pin "1") (pinfunction "1_1") (pintype "passive"))
    )
    (net (code "47") (name "GND_AMP") (class "Default")
      (node (ref "AMP") (pin "P$2") (pinfunction "A1_P$2") (pintype "bidirectional"))
      (node (ref "AMP") (pin "P$3") (pinfunction "A2_P$3") (pintype "bidirectional"))
      (node (ref "AMP") (pin "P$4") (pinfunction "A3_P$4") (pintype "bidirectional"))
      (node (ref "AMP") (pin "P$5") (pinfunction "A4_P$5") (pintype "bidirectional"))
      (node (ref "PX1") (pin "5") (pinfunction "P$5_5") (pintype "bidirectional"))
      (node (ref "PX10") (pin "5") (pinfunction "P$5_5") (pintype "bidirectional"))
      (node (ref "PX11") (pin "5") (pinfunction "P$5_5") (pintype "bidirectional"))
      (node (ref "PX12") (pin "5") (pinfunction "P$5_5") (pintype "bidirectional"))
      (node (ref "PX13") (pin "5") (pinfunction "P$5_5") (pintype "bidirectional"))
      (node (ref "PX14") (pin "5") (pinfunction "P$5_5") (pintype "bidirectional"))
      (node (ref "PX15") (pin "5") (pinfunction "P$5_5") (pintype "bidirectional"))
      (node (ref "PX16") (pin "5") (pinfunction "P$5_5") (pintype "bidirectional"))
      (node (ref "PX17") (pin "5") (pinfunction "P$5_5") (pintype "bidirectional"))
      (node (ref "PX18") (pin "5") (pinfunction "P$5_5") (pintype "bidirectional"))
      (node (ref "PX19") (pin "5") (pinfunction "P$5_5") (pintype "bidirectional"))
      (node (ref "PX2") (pin "5") (pinfunction "P$5_5") (pintype "bidirectional"))
      (node (ref "PX20") (pin "5") (pinfunction "P$5_5") (pintype "bidirectional"))
      (node (ref "PX21") (pin "5") (pinfunction "P$5_5") (pintype "bidirectional"))
      (node (ref "PX22") (pin "5") (pinfunction "P$5_5") (pintype "bidirectional"))
      (node (ref "PX23") (pin "5") (pinfunction "P$5_5") (pintype "bidirectional"))
      (node (ref "PX24") (pin "5") (pinfunction "P$5_5") (pintype "bidirectional"))
      (node (ref "PX25") (pin "5") (pinfunction "P$5_5") (pintype "bidirectional"))
      (node (ref "PX26") (pin "5") (pinfunction "P$5_5") (pintype "bidirectional"))
      (node (ref "PX27") (pin "5") (pinfunction "P$5_5") (pintype "bidirectional"))
      (node (ref "PX28") (pin "5") (pinfunction "P$5_5") (pintype "bidirectional"))
      (node (ref "PX29") (pin "5") (pinfunction "P$5_5") (pintype "bidirectional"))
      (node (ref "PX3") (pin "5") (pinfunction "P$5_5") (pintype "bidirectional"))
      (node (ref "PX30") (pin "5") (pinfunction "P$5_5") (pintype "bidirectional"))
      (node (ref "PX31") (pin "5") (pinfunction "P$5_5") (pintype "bidirectional"))
      (node (ref "PX32") (pin "5") (pinfunction "P$5_5") (pintype "bidirectional"))
      (node (ref "PX33") (pin "5") (pinfunction "P$5_5") (pintype "bidirectional"))
      (node (ref "PX34") (pin "5") (pinfunction "P$5_5") (pintype "bidirectional"))
      (node (ref "PX35") (pin "5") (pinfunction "P$5_5") (pintype "bidirectional"))
      (node (ref "PX36") (pin "5") (pinfunction "P$5_5") (pintype "bidirectional"))
      (node (ref "PX37") (pin "5") (pinfunction "P$5_5") (pintype "bidirectional"))
      (node (ref "PX38") (pin "5") (pinfunction "P$5_5") (pintype "bidirectional"))
      (node (ref "PX39") (pin "5") (pinfunction "P$5_5") (pintype "bidirectional"))
      (node (ref "PX4") (pin "5") (pinfunction "P$5_5") (pintype "bidirectional"))
      (node (ref "PX40") (pin "5") (pinfunction "P$5_5") (pintype "bidirectional"))
      (node (ref "PX5") (pin "5") (pinfunction "P$5_5") (pintype "bidirectional"))
      (node (ref "PX6") (pin "5") (pinfunction "P$5_5") (pintype "bidirectional"))
      (node (ref "PX7") (pin "5") (pinfunction "P$5_5") (pintype "bidirectional"))
      (node (ref "PX8") (pin "5") (pinfunction "P$5_5") (pintype "bidirectional"))
      (node (ref "PX9") (pin "5") (pinfunction "P$5_5") (pintype "bidirectional"))
    )
    (net (code "48") (name "Net-(IX1-PadVCC)") (class "Default")
      (node (ref "IX1") (pin "VCC") (pinfunction "VCC_VCC") (pintype "bidirectional"))
      (node (ref "R4") (pin "1") (pinfunction "1_1") (pintype "passive"))
    )
    (net (code "49") (name "Net-(IX2-PadVCC)") (class "Default")
      (node (ref "IX2") (pin "VCC") (pinfunction "VCC_VCC") (pintype "bidirectional"))
      (node (ref "R5") (pin "1") (pinfunction "1_1") (pintype "passive"))
    )
    (net (code "50") (name "Net-(IX3-PadVCC)") (class "Default")
      (node (ref "IX3") (pin "VCC") (pinfunction "VCC_VCC") (pintype "bidirectional"))
      (node (ref "R26") (pin "1") (pinfunction "1_1") (pintype "passive"))
    )
    (net (code "51") (name "Net-(IX4-PadVCC)") (class "Default")
      (node (ref "IX4") (pin "VCC") (pinfunction "VCC_VCC") (pintype "bidirectional"))
      (node (ref "R47") (pin "1") (pinfunction "1_1") (pintype "passive"))
    )
    (net (code "52") (name "Net-(IX5-PadVCC)") (class "Default")
      (node (ref "IX5") (pin "VCC") (pinfunction "VCC_VCC") (pintype "bidirectional"))
      (node (ref "R48") (pin "1") (pinfunction "1_1") (pintype "passive"))
    )
    (net (code "53") (name "Net-(IX6-PadVCC)") (class "Default")
      (node (ref "IX6") (pin "VCC") (pinfunction "VCC_VCC") (pintype "bidirectional"))
      (node (ref "R52") (pin "1") (pinfunction "1_1") (pintype "passive"))
    )
    (net (code "54") (name "Net-(MX1-ISET)") (class "Default")
      (node (ref "MX1") (pin "1") (pinfunction "ISET_1") (pintype "bidirectional"))
      (node (ref "R3") (pin "2") (pinfunction "2_2") (pintype "passive"))
    )
    (net (code "55") (name "Net-(MX1-P1)") (class "Default")
      (node (ref "IX1") (pin "I0") (pinfunction "I0_I0") (pintype "bidirectional"))
      (node (ref "MX1") (pin "5") (pinfunction "P1_5") (pintype "bidirectional"))
      (node (ref "R6") (pin "1") (pinfunction "1_1") (pintype "passive"))
    )
    (net (code "56") (name "Net-(MX1-P2)") (class "Default")
      (node (ref "IX1") (pin "I1") (pinfunction "I1_I1") (pintype "bidirectional"))
      (node (ref "MX1") (pin "6") (pinfunction "P2_6") (pintype "bidirectional"))
      (node (ref "R7") (pin "1") (pinfunction "1_1") (pintype "passive"))
    )
    (net (code "57") (name "Net-(MX1-P3)") (class "Default")
      (node (ref "IX1") (pin "I2") (pinfunction "I2_I2") (pintype "bidirectional"))
      (node (ref "MX1") (pin "7") (pinfunction "P3_7") (pintype "bidirectional"))
      (node (ref "R8") (pin "1") (pinfunction "1_1") (pintype "passive"))
    )
    (net (code "58") (name "Net-(MX1-P4)") (class "Default")
      (node (ref "IX1") (pin "I3") (pinfunction "I3_I3") (pintype "bidirectional"))
      (node (ref "MX1") (pin "8") (pinfunction "P4_8") (pintype "bidirectional"))
      (node (ref "R9") (pin "1") (pinfunction "1_1") (pintype "passive"))
    )
    (net (code "59") (name "Net-(MX1-P5)") (class "Default")
      (node (ref "IX1") (pin "I4") (pinfunction "I4_I4") (pintype "bidirectional"))
      (node (ref "MX1") (pin "9") (pinfunction "P5_9") (pintype "bidirectional"))
      (node (ref "R10") (pin "1") (pinfunction "1_1") (pintype "passive"))
    )
    (net (code "60") (name "Net-(MX1-P6)") (class "Default")
      (node (ref "IX1") (pin "I5") (pinfunction "I5_I5") (pintype "bidirectional"))
      (node (ref "MX1") (pin "10") (pinfunction "P6_10") (pintype "bidirectional"))
      (node (ref "R11") (pin "1") (pinfunction "1_1") (pintype "passive"))
    )
    (net (code "61") (name "Net-(MX1-P7)") (class "Default")
      (node (ref "IX1") (pin "I6") (pinfunction "I6_I6") (pintype "bidirectional"))
      (node (ref "MX1") (pin "11") (pinfunction "P7_11") (pintype "bidirectional"))
      (node (ref "R12") (pin "1") (pinfunction "1_1") (pintype "passive"))
    )
    (net (code "62") (name "Net-(MX1-P8)") (class "Default")
      (node (ref "IX1") (pin "I7") (pinfunction "I7_I7") (pintype "bidirectional"))
      (node (ref "MX1") (pin "12") (pinfunction "P8_12") (pintype "bidirectional"))
      (node (ref "R13") (pin "1") (pinfunction "1_1") (pintype "passive"))
    )
    (net (code "63") (name "Net-(MX1-P9)") (class "Default")
      (node (ref "IX2") (pin "I0") (pinfunction "I0_I0") (pintype "bidirectional"))
      (node (ref "MX1") (pin "13") (pinfunction "P9_13") (pintype "bidirectional"))
      (node (ref "R14") (pin "1") (pinfunction "1_1") (pintype "passive"))
    )
    (net (code "64") (name "Net-(MX1-P10)") (class "Default")
      (node (ref "IX2") (pin "I1") (pinfunction "I1_I1") (pintype "bidirectional"))
      (node (ref "MX1") (pin "14") (pinfunction "P10_14") (pintype "bidirectional"))
      (node (ref "R15") (pin "1") (pinfunction "1_1") (pintype "passive"))
    )
    (net (code "65") (name "Net-(MX1-P11)") (class "Default")
      (node (ref "IX2") (pin "I2") (pinfunction "I2_I2") (pintype "bidirectional"))
      (node (ref "MX1") (pin "15") (pinfunction "P11_15") (pintype "bidirectional"))
      (node (ref "R16") (pin "1") (pinfunction "1_1") (pintype "passive"))
    )
    (net (code "66") (name "Net-(MX1-P12)") (class "Default")
      (node (ref "IX2") (pin "I3") (pinfunction "I3_I3") (pintype "bidirectional"))
      (node (ref "MX1") (pin "16") (pinfunction "P12_16") (pintype "bidirectional"))
      (node (ref "R17") (pin "1") (pinfunction "1_1") (pintype "passive"))
    )
    (net (code "67") (name "Net-(MX1-P13)") (class "Default")
      (node (ref "IX2") (pin "I4") (pinfunction "I4_I4") (pintype "bidirectional"))
      (node (ref "MX1") (pin "17") (pinfunction "P13_17") (pintype "bidirectional"))
      (node (ref "R18") (pin "1") (pinfunction "1_1") (pintype "passive"))
    )
    (net (code "68") (name "Net-(MX1-P14)") (class "Default")
      (node (ref "IX2") (pin "I5") (pinfunction "I5_I5") (pintype "bidirectional"))
      (node (ref "MX1") (pin "18") (pinfunction "P14_18") (pintype "bidirectional"))
      (node (ref "R19") (pin "1") (pinfunction "1_1") (pintype "passive"))
    )
    (net (code "69") (name "Net-(MX1-P15)") (class "Default")
      (node (ref "IX2") (pin "I6") (pinfunction "I6_I6") (pintype "bidirectional"))
      (node (ref "MX1") (pin "19") (pinfunction "P15_19") (pintype "bidirectional"))
      (node (ref "R20") (pin "1") (pinfunction "1_1") (pintype "passive"))
    )
    (net (code "70") (name "Net-(MX1-P16)") (class "Default")
      (node (ref "IX2") (pin "I7") (pinfunction "I7_I7") (pintype "bidirectional"))
      (node (ref "MX1") (pin "20") (pinfunction "P16_20") (pintype "bidirectional"))
      (node (ref "R21") (pin "1") (pinfunction "1_1") (pintype "passive"))
    )
    (net (code "71") (name "Net-(MX1-P17)") (class "Default")
      (node (ref "IX3") (pin "I0") (pinfunction "I0_I0") (pintype "bidirectional"))
      (node (ref "MX1") (pin "21") (pinfunction "P17_21") (pintype "bidirectional"))
      (node (ref "R22") (pin "1") (pinfunction "1_1") (pintype "passive"))
    )
    (net (code "72") (name "Net-(MX1-P18)") (class "Default")
      (node (ref "IX3") (pin "I1") (pinfunction "I1_I1") (pintype "bidirectional"))
      (node (ref "MX1") (pin "22") (pinfunction "P18_22") (pintype "bidirectional"))
      (node (ref "R23") (pin "1") (pinfunction "1_1") (pintype "passive"))
    )
    (net (code "73") (name "Net-(MX1-P19)") (class "Default")
      (node (ref "IX3") (pin "I2") (pinfunction "I2_I2") (pintype "bidirectional"))
      (node (ref "MX1") (pin "23") (pinfunction "P19_23") (pintype "bidirectional"))
      (node (ref "R24") (pin "1") (pinfunction "1_1") (pintype "passive"))
    )
    (net (code "74") (name "Net-(MX1-P20)") (class "Default")
      (node (ref "IX3") (pin "I3") (pinfunction "I3_I3") (pintype "bidirectional"))
      (node (ref "MX1") (pin "24") (pinfunction "P20_24") (pintype "bidirectional"))
      (node (ref "R25") (pin "1") (pinfunction "1_1") (pintype "passive"))
    )
    (net (code "75") (name "Net-(MX2-ISET)") (class "Default")
      (node (ref "MX2") (pin "1") (pinfunction "ISET_1") (pintype "bidirectional"))
      (node (ref "R49") (pin "2") (pinfunction "2_2") (pintype "passive"))
    )
    (net (code "76") (name "Net-(MX2-P1)") (class "Default")
      (node (ref "IX6") (pin "I0") (pinfunction "I0_I0") (pintype "bidirectional"))
      (node (ref "MX2") (pin "5") (pinfunction "P1_5") (pintype "bidirectional"))
      (node (ref "R27") (pin "1") (pinfunction "1_1") (pintype "passive"))
    )
    (net (code "77") (name "Net-(MX2-P2)") (class "Default")
      (node (ref "IX6") (pin "I1") (pinfunction "I1_I1") (pintype "bidirectional"))
      (node (ref "MX2") (pin "6") (pinfunction "P2_6") (pintype "bidirectional"))
      (node (ref "R28") (pin "1") (pinfunction "1_1") (pintype "passive"))
    )
    (net (code "78") (name "Net-(MX2-P3)") (class "Default")
      (node (ref "IX6") (pin "I2") (pinfunction "I2_I2") (pintype "bidirectional"))
      (node (ref "MX2") (pin "7") (pinfunction "P3_7") (pintype "bidirectional"))
      (node (ref "R29") (pin "1") (pinfunction "1_1") (pintype "passive"))
    )
    (net (code "79") (name "Net-(MX2-P4)") (class "Default")
      (node (ref "IX6") (pin "I3") (pinfunction "I3_I3") (pintype "bidirectional"))
      (node (ref "MX2") (pin "8") (pinfunction "P4_8") (pintype "bidirectional"))
      (node (ref "R30") (pin "1") (pinfunction "1_1") (pintype "passive"))
    )
    (net (code "80") (name "Net-(MX2-P5)") (class "Default")
      (node (ref "IX5") (pin "I0") (pinfunction "I0_I0") (pintype "bidirectional"))
      (node (ref "MX2") (pin "9") (pinfunction "P5_9") (pintype "bidirectional"))
      (node (ref "R31") (pin "1") (pinfunction "1_1") (pintype "passive"))
    )
    (net (code "81") (name "Net-(MX2-P6)") (class "Default")
      (node (ref "IX5") (pin "I1") (pinfunction "I1_I1") (pintype "bidirectional"))
      (node (ref "MX2") (pin "10") (pinfunction "P6_10") (pintype "bidirectional"))
      (node (ref "R32") (pin "1") (pinfunction "1_1") (pintype "passive"))
    )
    (net (code "82") (name "Net-(MX2-P7)") (class "Default")
      (node (ref "IX5") (pin "I2") (pinfunction "I2_I2") (pintype "bidirectional"))
      (node (ref "MX2") (pin "11") (pinfunction "P7_11") (pintype "bidirectional"))
      (node (ref "R33") (pin "1") (pinfunction "1_1") (pintype "passive"))
    )
    (net (code "83") (name "Net-(MX2-P8)") (class "Default")
      (node (ref "IX5") (pin "I3") (pinfunction "I3_I3") (pintype "bidirectional"))
      (node (ref "MX2") (pin "12") (pinfunction "P8_12") (pintype "bidirectional"))
      (node (ref "R34") (pin "1") (pinfunction "1_1") (pintype "passive"))
    )
    (net (code "84") (name "Net-(MX2-P9)") (class "Default")
      (node (ref "IX5") (pin "I4") (pinfunction "I4_I4") (pintype "bidirectional"))
      (node (ref "MX2") (pin "13") (pinfunction "P9_13") (pintype "bidirectional"))
      (node (ref "R35") (pin "1") (pinfunction "1_1") (pintype "passive"))
    )
    (net (code "85") (name "Net-(MX2-P10)") (class "Default")
      (node (ref "IX5") (pin "I5") (pinfunction "I5_I5") (pintype "bidirectional"))
      (node (ref "MX2") (pin "14") (pinfunction "P10_14") (pintype "bidirectional"))
      (node (ref "R36") (pin "1") (pinfunction "1_1") (pintype "passive"))
    )
    (net (code "86") (name "Net-(MX2-P11)") (class "Default")
      (node (ref "IX5") (pin "I6") (pinfunction "I6_I6") (pintype "bidirectional"))
      (node (ref "MX2") (pin "15") (pinfunction "P11_15") (pintype "bidirectional"))
      (node (ref "R37") (pin "1") (pinfunction "1_1") (pintype "passive"))
    )
    (net (code "87") (name "Net-(MX2-P12)") (class "Default")
      (node (ref "IX5") (pin "I7") (pinfunction "I7_I7") (pintype "bidirectional"))
      (node (ref "MX2") (pin "16") (pinfunction "P12_16") (pintype "bidirectional"))
      (node (ref "R38") (pin "1") (pinfunction "1_1") (pintype "passive"))
    )
    (net (code "88") (name "Net-(MX2-P13)") (class "Default")
      (node (ref "IX4") (pin "I0") (pinfunction "I0_I0") (pintype "bidirectional"))
      (node (ref "MX2") (pin "17") (pinfunction "P13_17") (pintype "bidirectional"))
      (node (ref "R39") (pin "1") (pinfunction "1_1") (pintype "passive"))
    )
    (net (code "89") (name "Net-(MX2-P14)") (class "Default")
      (node (ref "IX4") (pin "I1") (pinfunction "I1_I1") (pintype "bidirectional"))
      (node (ref "MX2") (pin "18") (pinfunction "P14_18") (pintype "bidirectional"))
      (node (ref "R40") (pin "1") (pinfunction "1_1") (pintype "passive"))
    )
    (net (code "90") (name "Net-(MX2-P15)") (class "Default")
      (node (ref "IX4") (pin "I2") (pinfunction "I2_I2") (pintype "bidirectional"))
      (node (ref "MX2") (pin "19") (pinfunction "P15_19") (pintype "bidirectional"))
      (node (ref "R41") (pin "1") (pinfunction "1_1") (pintype "passive"))
    )
    (net (code "91") (name "Net-(MX2-P16)") (class "Default")
      (node (ref "IX4") (pin "I3") (pinfunction "I3_I3") (pintype "bidirectional"))
      (node (ref "MX2") (pin "20") (pinfunction "P16_20") (pintype "bidirectional"))
      (node (ref "R42") (pin "1") (pinfunction "1_1") (pintype "passive"))
    )
    (net (code "92") (name "Net-(MX2-P17)") (class "Default")
      (node (ref "IX4") (pin "I4") (pinfunction "I4_I4") (pintype "bidirectional"))
      (node (ref "MX2") (pin "21") (pinfunction "P17_21") (pintype "bidirectional"))
      (node (ref "R43") (pin "1") (pinfunction "1_1") (pintype "passive"))
    )
    (net (code "93") (name "Net-(MX2-P18)") (class "Default")
      (node (ref "IX4") (pin "I5") (pinfunction "I5_I5") (pintype "bidirectional"))
      (node (ref "MX2") (pin "22") (pinfunction "P18_22") (pintype "bidirectional"))
      (node (ref "R44") (pin "1") (pinfunction "1_1") (pintype "passive"))
    )
    (net (code "94") (name "Net-(MX2-P19)") (class "Default")
      (node (ref "IX4") (pin "I6") (pinfunction "I6_I6") (pintype "bidirectional"))
      (node (ref "MX2") (pin "23") (pinfunction "P19_23") (pintype "bidirectional"))
      (node (ref "R45") (pin "1") (pinfunction "1_1") (pintype "passive"))
    )
    (net (code "95") (name "Net-(MX2-P20)") (class "Default")
      (node (ref "IX4") (pin "I7") (pinfunction "I7_I7") (pintype "bidirectional"))
      (node (ref "MX2") (pin "24") (pinfunction "P20_24") (pintype "bidirectional"))
      (node (ref "R46") (pin "1") (pinfunction "1_1") (pintype "passive"))
    )
    (net (code "96") (name "Net-(PX1-P$1)") (class "Default")
      (node (ref "PX1") (pin "1") (pinfunction "P$1_1") (pintype "bidirectional"))
      (node (ref "R6") (pin "2") (pinfunction "2_2") (pintype "passive"))
    )
    (net (code "97") (name "Net-(PX2-P$1)") (class "Default")
      (node (ref "PX2") (pin "1") (pinfunction "P$1_1") (pintype "bidirectional"))
      (node (ref "R7") (pin "2") (pinfunction "2_2") (pintype "passive"))
    )
    (net (code "98") (name "Net-(PX3-P$1)") (class "Default")
      (node (ref "PX3") (pin "1") (pinfunction "P$1_1") (pintype "bidirectional"))
      (node (ref "R8") (pin "2") (pinfunction "2_2") (pintype "passive"))
    )
    (net (code "99") (name "Net-(PX4-P$1)") (class "Default")
      (node (ref "PX4") (pin "1") (pinfunction "P$1_1") (pintype "bidirectional"))
      (node (ref "R9") (pin "2") (pinfunction "2_2") (pintype "passive"))
    )
    (net (code "100") (name "Net-(PX5-P$1)") (class "Default")
      (node (ref "PX5") (pin "1") (pinfunction "P$1_1") (pintype "bidirectional"))
      (node (ref "R10") (pin "2") (pinfunction "2_2") (pintype "passive"))
    )
    (net (code "101") (name "Net-(PX6-P$1)") (class "Default")
      (node (ref "PX6") (pin "1") (pinfunction "P$1_1") (pintype "bidirectional"))
      (node (ref "R11") (pin "2") (pinfunction "2_2") (pintype "passive"))
    )
    (net (code "102") (name "Net-(PX7-P$1)") (class "Default")
      (node (ref "PX7") (pin "1") (pinfunction "P$1_1") (pintype "bidirectional"))
      (node (ref "R12") (pin "2") (pinfunction "2_2") (pintype "passive"))
    )
    (net (code "103") (name "Net-(PX8-P$1)") (class "Default")
      (node (ref "PX8") (pin "1") (pinfunction "P$1_1") (pintype "bidirectional"))
      (node (ref "R13") (pin "2") (pinfunction "2_2") (pintype "passive"))
    )
    (net (code "104") (name "Net-(PX9-P$1)") (class "Default")
      (node (ref "PX9") (pin "1") (pinfunction "P$1_1") (pintype "bidirectional"))
      (node (ref "R14") (pin "2") (pinfunction "2_2") (pintype "passive"))
    )
    (net (code "105") (name "Net-(PX10-P$1)") (class "Default")
      (node (ref "PX10") (pin "1") (pinfunction "P$1_1") (pintype "bidirectional"))
      (node (ref "R15") (pin "2") (pinfunction "2_2") (pintype "passive"))
    )
    (net (code "106") (name "Net-(PX11-P$1)") (class "Default")
      (node (ref "PX11") (pin "1") (pinfunction "P$1_1") (pintype "bidirectional"))
      (node (ref "R16") (pin "2") (pinfunction "2_2") (pintype "passive"))
    )
    (net (code "107") (name "Net-(PX12-P$1)") (class "Default")
      (node (ref "PX12") (pin "1") (pinfunction "P$1_1") (pintype "bidirectional"))
      (node (ref "R17") (pin "2") (pinfunction "2_2") (pintype "passive"))
    )
    (net (code "108") (name "Net-(PX13-P$1)") (class "Default")
      (node (ref "PX13") (pin "1") (pinfunction "P$1_1") (pintype "bidirectional"))
      (node (ref "R18") (pin "2") (pinfunction "2_2") (pintype "passive"))
    )
    (net (code "109") (name "Net-(PX14-P$1)") (class "Default")
      (node (ref "PX14") (pin "1") (pinfunction "P$1_1") (pintype "bidirectional"))
      (node (ref "R19") (pin "2") (pinfunction "2_2") (pintype "passive"))
    )
    (net (code "110") (name "Net-(PX15-P$1)") (class "Default")
      (node (ref "PX15") (pin "1") (pinfunction "P$1_1") (pintype "bidirectional"))
      (node (ref "R20") (pin "2") (pinfunction "2_2") (pintype "passive"))
    )
    (net (code "111") (name "Net-(PX16-P$1)") (class "Default")
      (node (ref "PX16") (pin "1") (pinfunction "P$1_1") (pintype "bidirectional"))
      (node (ref "R21") (pin "2") (pinfunction "2_2") (pintype "passive"))
    )
    (net (code "112") (name "Net-(PX17-P$1)") (class "Default")
      (node (ref "PX17") (pin "1") (pinfunction "P$1_1") (pintype "bidirectional"))
      (node (ref "R22") (pin "2") (pinfunction "2_2") (pintype "passive"))
    )
    (net (code "113") (name "Net-(PX18-P$1)") (class "Default")
      (node (ref "PX18") (pin "1") (pinfunction "P$1_1") (pintype "bidirectional"))
      (node (ref "R23") (pin "2") (pinfunction "2_2") (pintype "passive"))
    )
    (net (code "114") (name "Net-(PX19-P$1)") (class "Default")
      (node (ref "PX19") (pin "1") (pinfunction "P$1_1") (pintype "bidirectional"))
      (node (ref "R24") (pin "2") (pinfunction "2_2") (pintype "passive"))
    )
    (net (code "115") (name "Net-(PX20-P$1)") (class "Default")
      (node (ref "PX20") (pin "1") (pinfunction "P$1_1") (pintype "bidirectional"))
      (node (ref "R25") (pin "2") (pinfunction "2_2") (pintype "passive"))
    )
    (net (code "116") (name "Net-(PX21-P$1)") (class "Default")
      (node (ref "PX21") (pin "1") (pinfunction "P$1_1") (pintype "bidirectional"))
      (node (ref "R27") (pin "2") (pinfunction "2_2") (pintype "passive"))
    )
    (net (code "117") (name "Net-(PX22-P$1)") (class "Default")
      (node (ref "PX22") (pin "1") (pinfunction "P$1_1") (pintype "bidirectional"))
      (node (ref "R28") (pin "2") (pinfunction "2_2") (pintype "passive"))
    )
    (net (code "118") (name "Net-(PX23-P$1)") (class "Default")
      (node (ref "PX23") (pin "1") (pinfunction "P$1_1") (pintype "bidirectional"))
      (node (ref "R29") (pin "2") (pinfunction "2_2") (pintype "passive"))
    )
    (net (code "119") (name "Net-(PX24-P$1)") (class "Default")
      (node (ref "PX24") (pin "1") (pinfunction "P$1_1") (pintype "bidirectional"))
      (node (ref "R30") (pin "2") (pinfunction "2_2") (pintype "passive"))
    )
    (net (code "120") (name "Net-(PX25-P$1)") (class "Default")
      (node (ref "PX25") (pin "1") (pinfunction "P$1_1") (pintype "bidirectional"))
      (node (ref "R31") (pin "2") (pinfunction "2_2") (pintype "passive"))
    )
    (net (code "121") (name "Net-(PX26-P$1)") (class "Default")
      (node (ref "PX26") (pin "1") (pinfunction "P$1_1") (pintype "bidirectional"))
      (node (ref "R32") (pin "2") (pinfunction "2_2") (pintype "passive"))
    )
    (net (code "122") (name "Net-(PX27-P$1)") (class "Default")
      (node (ref "PX27") (pin "1") (pinfunction "P$1_1") (pintype "bidirectional"))
      (node (ref "R33") (pin "2") (pinfunction "2_2") (pintype "passive"))
    )
    (net (code "123") (name "Net-(PX28-P$1)") (class "Default")
      (node (ref "PX28") (pin "1") (pinfunction "P$1_1") (pintype "bidirectional"))
      (node (ref "R34") (pin "2") (pinfunction "2_2") (pintype "passive"))
    )
    (net (code "124") (name "Net-(PX29-P$1)") (class "Default")
      (node (ref "PX29") (pin "1") (pinfunction "P$1_1") (pintype "bidirectional"))
      (node (ref "R35") (pin "2") (pinfunction "2_2") (pintype "passive"))
    )
    (net (code "125") (name "Net-(PX30-P$1)") (class "Default")
      (node (ref "PX30") (pin "1") (pinfunction "P$1_1") (pintype "bidirectional"))
      (node (ref "R36") (pin "2") (pinfunction "2_2") (pintype "passive"))
    )
    (net (code "126") (name "Net-(PX31-P$1)") (class "Default")
      (node (ref "PX31") (pin "1") (pinfunction "P$1_1") (pintype "bidirectional"))
      (node (ref "R37") (pin "2") (pinfunction "2_2") (pintype "passive"))
    )
    (net (code "127") (name "Net-(PX32-P$1)") (class "Default")
      (node (ref "PX32") (pin "1") (pinfunction "P$1_1") (pintype "bidirectional"))
      (node (ref "R38") (pin "2") (pinfunction "2_2") (pintype "passive"))
    )
    (net (code "128") (name "Net-(PX33-P$1)") (class "Default")
      (node (ref "PX33") (pin "1") (pinfunction "P$1_1") (pintype "bidirectional"))
      (node (ref "R39") (pin "2") (pinfunction "2_2") (pintype "passive"))
    )
    (net (code "129") (name "Net-(PX34-P$1)") (class "Default")
      (node (ref "PX34") (pin "1") (pinfunction "P$1_1") (pintype "bidirectional"))
      (node (ref "R40") (pin "2") (pinfunction "2_2") (pintype "passive"))
    )
    (net (code "130") (name "Net-(PX35-P$1)") (class "Default")
      (node (ref "PX35") (pin "1") (pinfunction "P$1_1") (pintype "bidirectional"))
      (node (ref "R41") (pin "2") (pinfunction "2_2") (pintype "passive"))
    )
    (net (code "131") (name "Net-(PX36-P$1)") (class "Default")
      (node (ref "PX36") (pin "1") (pinfunction "P$1_1") (pintype "bidirectional"))
      (node (ref "R42") (pin "2") (pinfunction "2_2") (pintype "passive"))
    )
    (net (code "132") (name "Net-(PX37-P$1)") (class "Default")
      (node (ref "PX37") (pin "1") (pinfunction "P$1_1") (pintype "bidirectional"))
      (node (ref "R43") (pin "2") (pinfunction "2_2") (pintype "passive"))
    )
    (net (code "133") (name "Net-(PX38-P$1)") (class "Default")
      (node (ref "PX38") (pin "1") (pinfunction "P$1_1") (pintype "bidirectional"))
      (node (ref "R44") (pin "2") (pinfunction "2_2") (pintype "passive"))
    )
    (net (code "134") (name "Net-(PX39-P$1)") (class "Default")
      (node (ref "PX39") (pin "1") (pinfunction "P$1_1") (pintype "bidirectional"))
      (node (ref "R45") (pin "2") (pinfunction "2_2") (pintype "passive"))
    )
    (net (code "135") (name "Net-(PX40-P$1)") (class "Default")
      (node (ref "PX40") (pin "1") (pinfunction "P$1_1") (pintype "bidirectional"))
      (node (ref "R46") (pin "2") (pinfunction "2_2") (pintype "passive"))
    )
    (net (code "136") (name "O0") (class "Default")
      (node (ref "IX1") (pin "O0") (pinfunction "O0_O0") (pintype "bidirectional"))
      (node (ref "PX1") (pin "3") (pinfunction "P$3_3") (pintype "bidirectional"))
    )
    (net (code "137") (name "O1") (class "Default")
      (node (ref "IX1") (pin "O1") (pinfunction "O1_O1") (pintype "bidirectional"))
      (node (ref "PX2") (pin "3") (pinfunction "P$3_3") (pintype "bidirectional"))
    )
    (net (code "138") (name "O2") (class "Default")
      (node (ref "IX1") (pin "O2") (pinfunction "O2_O2") (pintype "bidirectional"))
      (node (ref "PX3") (pin "3") (pinfunction "P$3_3") (pintype "bidirectional"))
    )
    (net (code "139") (name "O3") (class "Default")
      (node (ref "IX1") (pin "O3") (pinfunction "O3_O3") (pintype "bidirectional"))
      (node (ref "PX4") (pin "3") (pinfunction "P$3_3") (pintype "bidirectional"))
    )
    (net (code "140") (name "O4") (class "Default")
      (node (ref "IX1") (pin "O4") (pinfunction "O4_O4") (pintype "bidirectional"))
      (node (ref "PX5") (pin "3") (pinfunction "P$3_3") (pintype "bidirectional"))
    )
    (net (code "141") (name "O5") (class "Default")
      (node (ref "IX1") (pin "O5") (pinfunction "O5_O5") (pintype "bidirectional"))
      (node (ref "PX6") (pin "3") (pinfunction "P$3_3") (pintype "bidirectional"))
    )
    (net (code "142") (name "O6") (class "Default")
      (node (ref "IX1") (pin "O6") (pinfunction "O6_O6") (pintype "bidirectional"))
      (node (ref "PX7") (pin "3") (pinfunction "P$3_3") (pintype "bidirectional"))
    )
    (net (code "143") (name "O7") (class "Default")
      (node (ref "IX1") (pin "O7") (pinfunction "O7_O7") (pintype "bidirectional"))
      (node (ref "PX8") (pin "3") (pinfunction "P$3_3") (pintype "bidirectional"))
    )
    (net (code "144") (name "O8") (class "Default")
      (node (ref "IX2") (pin "O0") (pinfunction "O0_O0") (pintype "bidirectional"))
      (node (ref "PX9") (pin "3") (pinfunction "P$3_3") (pintype "bidirectional"))
    )
    (net (code "145") (name "O9") (class "Default")
      (node (ref "IX2") (pin "O1") (pinfunction "O1_O1") (pintype "bidirectional"))
      (node (ref "PX10") (pin "3") (pinfunction "P$3_3") (pintype "bidirectional"))
    )
    (net (code "146") (name "O10") (class "Default")
      (node (ref "IX2") (pin "O2") (pinfunction "O2_O2") (pintype "bidirectional"))
      (node (ref "PX11") (pin "3") (pinfunction "P$3_3") (pintype "bidirectional"))
    )
    (net (code "147") (name "O11") (class "Default")
      (node (ref "IX2") (pin "O3") (pinfunction "O3_O3") (pintype "bidirectional"))
      (node (ref "PX12") (pin "3") (pinfunction "P$3_3") (pintype "bidirectional"))
    )
    (net (code "148") (name "O12") (class "Default")
      (node (ref "IX2") (pin "O4") (pinfunction "O4_O4") (pintype "bidirectional"))
      (node (ref "PX13") (pin "3") (pinfunction "P$3_3") (pintype "bidirectional"))
    )
    (net (code "149") (name "O13") (class "Default")
      (node (ref "IX2") (pin "O5") (pinfunction "O5_O5") (pintype "bidirectional"))
      (node (ref "PX14") (pin "3") (pinfunction "P$3_3") (pintype "bidirectional"))
    )
    (net (code "150") (name "O14") (class "Default")
      (node (ref "IX2") (pin "O6") (pinfunction "O6_O6") (pintype "bidirectional"))
      (node (ref "PX15") (pin "3") (pinfunction "P$3_3") (pintype "bidirectional"))
    )
    (net (code "151") (name "O15") (class "Default")
      (node (ref "IX2") (pin "O7") (pinfunction "O7_O7") (pintype "bidirectional"))
      (node (ref "PX16") (pin "3") (pinfunction "P$3_3") (pintype "bidirectional"))
    )
    (net (code "152") (name "O16") (class "Default")
      (node (ref "IX3") (pin "O0") (pinfunction "O0_O0") (pintype "bidirectional"))
      (node (ref "PX17") (pin "3") (pinfunction "P$3_3") (pintype "bidirectional"))
    )
    (net (code "153") (name "O17") (class "Default")
      (node (ref "IX3") (pin "O1") (pinfunction "O1_O1") (pintype "bidirectional"))
      (node (ref "PX18") (pin "3") (pinfunction "P$3_3") (pintype "bidirectional"))
    )
    (net (code "154") (name "O18") (class "Default")
      (node (ref "IX3") (pin "O2") (pinfunction "O2_O2") (pintype "bidirectional"))
      (node (ref "PX19") (pin "3") (pinfunction "P$3_3") (pintype "bidirectional"))
    )
    (net (code "155") (name "O19") (class "Default")
      (node (ref "IX3") (pin "O3") (pinfunction "O3_O3") (pintype "bidirectional"))
      (node (ref "PX20") (pin "3") (pinfunction "P$3_3") (pintype "bidirectional"))
    )
    (net (code "156") (name "O20") (class "Default")
      (node (ref "IX6") (pin "O0") (pinfunction "O0_O0") (pintype "bidirectional"))
      (node (ref "PX21") (pin "3") (pinfunction "P$3_3") (pintype "bidirectional"))
    )
    (net (code "157") (name "O21") (class "Default")
      (node (ref "IX6") (pin "O1") (pinfunction "O1_O1") (pintype "bidirectional"))
      (node (ref "PX22") (pin "3") (pinfunction "P$3_3") (pintype "bidirectional"))
    )
    (net (code "158") (name "O22") (class "Default")
      (node (ref "IX6") (pin "O2") (pinfunction "O2_O2") (pintype "bidirectional"))
      (node (ref "PX23") (pin "3") (pinfunction "P$3_3") (pintype "bidirectional"))
    )
    (net (code "159") (name "O23") (class "Default")
      (node (ref "IX6") (pin "O3") (pinfunction "O3_O3") (pintype "bidirectional"))
      (node (ref "PX24") (pin "3") (pinfunction "P$3_3") (pintype "bidirectional"))
    )
    (net (code "160") (name "O24") (class "Default")
      (node (ref "IX5") (pin "O0") (pinfunction "O0_O0") (pintype "bidirectional"))
      (node (ref "PX25") (pin "3") (pinfunction "P$3_3") (pintype "bidirectional"))
    )
    (net (code "161") (name "O25") (class "Default")
      (node (ref "IX5") (pin "O1") (pinfunction "O1_O1") (pintype "bidirectional"))
      (node (ref "PX26") (pin "3") (pinfunction "P$3_3") (pintype "bidirectional"))
    )
    (net (code "162") (name "O26") (class "Default")
      (node (ref "IX5") (pin "O2") (pinfunction "O2_O2") (pintype "bidirectional"))
      (node (ref "PX27") (pin "3") (pinfunction "P$3_3") (pintype "bidirectional"))
    )
    (net (code "163") (name "O27") (class "Default")
      (node (ref "IX5") (pin "O3") (pinfunction "O3_O3") (pintype "bidirectional"))
      (node (ref "PX28") (pin "3") (pinfunction "P$3_3") (pintype "bidirectional"))
    )
    (net (code "164") (name "O28") (class "Default")
      (node (ref "IX5") (pin "O4") (pinfunction "O4_O4") (pintype "bidirectional"))
      (node (ref "PX29") (pin "3") (pinfunction "P$3_3") (pintype "bidirectional"))
    )
    (net (code "165") (name "O29") (class "Default")
      (node (ref "IX5") (pin "O5") (pinfunction "O5_O5") (pintype "bidirectional"))
      (node (ref "PX30") (pin "3") (pinfunction "P$3_3") (pintype "bidirectional"))
    )
    (net (code "166") (name "O30") (class "Default")
      (node (ref "IX5") (pin "O6") (pinfunction "O6_O6") (pintype "bidirectional"))
      (node (ref "PX31") (pin "3") (pinfunction "P$3_3") (pintype "bidirectional"))
    )
    (net (code "167") (name "O31") (class "Default")
      (node (ref "IX5") (pin "O7") (pinfunction "O7_O7") (pintype "bidirectional"))
      (node (ref "PX32") (pin "3") (pinfunction "P$3_3") (pintype "bidirectional"))
    )
    (net (code "168") (name "O32") (class "Default")
      (node (ref "IX4") (pin "O0") (pinfunction "O0_O0") (pintype "bidirectional"))
      (node (ref "PX33") (pin "3") (pinfunction "P$3_3") (pintype "bidirectional"))
    )
    (net (code "169") (name "O33") (class "Default")
      (node (ref "IX4") (pin "O1") (pinfunction "O1_O1") (pintype "bidirectional"))
      (node (ref "PX34") (pin "3") (pinfunction "P$3_3") (pintype "bidirectional"))
    )
    (net (code "170") (name "O34") (class "Default")
      (node (ref "IX4") (pin "O2") (pinfunction "O2_O2") (pintype "bidirectional"))
      (node (ref "PX35") (pin "3") (pinfunction "P$3_3") (pintype "bidirectional"))
    )
    (net (code "171") (name "O35") (class "Default")
      (node (ref "IX4") (pin "O3") (pinfunction "O3_O3") (pintype "bidirectional"))
      (node (ref "PX36") (pin "3") (pinfunction "P$3_3") (pintype "bidirectional"))
    )
    (net (code "172") (name "O36") (class "Default")
      (node (ref "IX4") (pin "O4") (pinfunction "O4_O4") (pintype "bidirectional"))
      (node (ref "PX37") (pin "3") (pinfunction "P$3_3") (pintype "bidirectional"))
    )
    (net (code "173") (name "O37") (class "Default")
      (node (ref "IX4") (pin "O5") (pinfunction "O5_O5") (pintype "bidirectional"))
      (node (ref "PX38") (pin "3") (pinfunction "P$3_3") (pintype "bidirectional"))
    )
    (net (code "174") (name "O38") (class "Default")
      (node (ref "IX4") (pin "O6") (pinfunction "O6_O6") (pintype "bidirectional"))
      (node (ref "PX39") (pin "3") (pinfunction "P$3_3") (pintype "bidirectional"))
    )
    (net (code "175") (name "O39") (class "Default")
      (node (ref "IX4") (pin "O7") (pinfunction "O7_O7") (pintype "bidirectional"))
      (node (ref "PX40") (pin "3") (pinfunction "P$3_3") (pintype "bidirectional"))
    )
    (net (code "176") (name "SCL") (class "Default")
      (node (ref "J1") (pin "3") (pinfunction "SCL_3") (pintype "bidirectional"))
      (node (ref "J2") (pin "3") (pinfunction "SCL_3") (pintype "bidirectional"))
      (node (ref "J3") (pin "3") (pinfunction "SCL_3") (pintype "bidirectional"))
      (node (ref "J4") (pin "3") (pinfunction "SCL_3") (pintype "bidirectional"))
      (node (ref "MX1") (pin "26") (pinfunction "SCL_26") (pintype "bidirectional"))
      (node (ref "MX2") (pin "26") (pinfunction "SCL_26") (pintype "bidirectional"))
      (node (ref "R2") (pin "2") (pinfunction "2_2") (pintype "passive"))
      (node (ref "R51") (pin "2") (pinfunction "2_2") (pintype "passive"))
      (node (ref "SCL") (pin "P$1") (pinfunction "PIN_P$1") (pintype "bidirectional"))
    )
    (net (code "177") (name "SDA") (class "Default")
      (node (ref "J1") (pin "4") (pinfunction "SDA_4") (pintype "bidirectional"))
      (node (ref "J2") (pin "4") (pinfunction "SDA_4") (pintype "bidirectional"))
      (node (ref "J3") (pin "4") (pinfunction "SDA_4") (pintype "bidirectional"))
      (node (ref "J4") (pin "4") (pinfunction "SDA_4") (pintype "bidirectional"))
      (node (ref "MX1") (pin "25") (pinfunction "SDA_25") (pintype "bidirectional"))
      (node (ref "MX2") (pin "25") (pinfunction "SDA_25") (pintype "bidirectional"))
      (node (ref "R1") (pin "2") (pinfunction "2_2") (pintype "passive"))
      (node (ref "R50") (pin "2") (pinfunction "2_2") (pintype "passive"))
      (node (ref "SDA") (pin "P$1") (pinfunction "PIN_P$1") (pintype "bidirectional"))
    )
    (net (code "178") (name "VDD") (class "Default")
      (node (ref "5V") (pin "HOT") (pinfunction "HOT_HOT") (pintype "bidirectional"))
      (node (ref "J1") (pin "2") (pinfunction "V+_2") (pintype "bidirectional"))
      (node (ref "J2") (pin "2") (pinfunction "V+_2") (pintype "bidirectional"))
      (node (ref "J3") (pin "2") (pinfunction "V+_2") (pintype "bidirectional"))
      (node (ref "J4") (pin "2") (pinfunction "V+_2") (pintype "bidirectional"))
      (node (ref "MX1") (pin "28") (pinfunction "V+_28") (pintype "bidirectional"))
      (node (ref "MX2") (pin "28") (pinfunction "V+_28") (pintype "bidirectional"))
      (node (ref "R1") (pin "1") (pinfunction "1_1") (pintype "passive"))
      (node (ref "R2") (pin "1") (pinfunction "1_1") (pintype "passive"))
      (node (ref "R26") (pin "2") (pinfunction "2_2") (pintype "passive"))
      (node (ref "R4") (pin "2") (pinfunction "2_2") (pintype "passive"))
      (node (ref "R47") (pin "2") (pinfunction "2_2") (pintype "passive"))
      (node (ref "R48") (pin "2") (pinfunction "2_2") (pintype "passive"))
      (node (ref "R5") (pin "2") (pinfunction "2_2") (pintype "passive"))
      (node (ref "R50") (pin "1") (pinfunction "1_1") (pintype "passive"))
      (node (ref "R51") (pin "1") (pinfunction "1_1") (pintype "passive"))
      (node (ref "R52") (pin "2") (pinfunction "2_2") (pintype "passive"))
    )
    (net (code "179") (name "unconnected-(IX3-PadI4)") (class "Default")
      (node (ref "IX3") (pin "I4") (pinfunction "I4_I4") (pintype "bidirectional"))
    )
    (net (code "180") (name "unconnected-(IX3-PadI5)") (class "Default")
      (node (ref "IX3") (pin "I5") (pinfunction "I5_I5") (pintype "bidirectional"))
    )
    (net (code "181") (name "unconnected-(IX3-PadI6)") (class "Default")
      (node (ref "IX3") (pin "I6") (pinfunction "I6_I6") (pintype "bidirectional"))
    )
    (net (code "182") (name "unconnected-(IX3-PadI7)") (class "Default")
      (node (ref "IX3") (pin "I7") (pinfunction "I7_I7") (pintype "bidirectional"))
    )
    (net (code "183") (name "unconnected-(IX3-PadO4)") (class "Default")
      (node (ref "IX3") (pin "O4") (pinfunction "O4_O4") (pintype "bidirectional"))
    )
    (net (code "184") (name "unconnected-(IX3-PadO5)") (class "Default")
      (node (ref "IX3") (pin "O5") (pinfunction "O5_O5") (pintype "bidirectional"))
    )
    (net (code "185") (name "unconnected-(IX3-PadO6)") (class "Default")
      (node (ref "IX3") (pin "O6") (pinfunction "O6_O6") (pintype "bidirectional"))
    )
    (net (code "186") (name "unconnected-(IX3-PadO7)") (class "Default")
      (node (ref "IX3") (pin "O7") (pinfunction "O7_O7") (pintype "bidirectional"))
    )
    (net (code "187") (name "unconnected-(IX6-PadI4)") (class "Default")
      (node (ref "IX6") (pin "I4") (pinfunction "I4_I4") (pintype "bidirectional"))
    )
    (net (code "188") (name "unconnected-(IX6-PadI5)") (class "Default")
      (node (ref "IX6") (pin "I5") (pinfunction "I5_I5") (pintype "bidirectional"))
    )
    (net (code "189") (name "unconnected-(IX6-PadI6)") (class "Default")
      (node (ref "IX6") (pin "I6") (pinfunction "I6_I6") (pintype "bidirectional"))
    )
    (net (code "190") (name "unconnected-(IX6-PadI7)") (class "Default")
      (node (ref "IX6") (pin "I7") (pinfunction "I7_I7") (pintype "bidirectional"))
    )
    (net (code "191") (name "unconnected-(IX6-PadO4)") (class "Default")
      (node (ref "IX6") (pin "O4") (pinfunction "O4_O4") (pintype "bidirectional"))
    )
    (net (code "192") (name "unconnected-(IX6-PadO5)") (class "Default")
      (node (ref "IX6") (pin "O5") (pinfunction "O5_O5") (pintype "bidirectional"))
    )
    (net (code "193") (name "unconnected-(IX6-PadO6)") (class "Default")
      (node (ref "IX6") (pin "O6") (pinfunction "O6_O6") (pintype "bidirectional"))
    )
    (net (code "194") (name "unconnected-(IX6-PadO7)") (class "Default")
      (node (ref "IX6") (pin "O7") (pinfunction "O7_O7") (pintype "bidirectional"))
    )
  )
)
